# bontor_mbed_rev_c.net
KiCad netlist of a schematic drawn in EAGLE
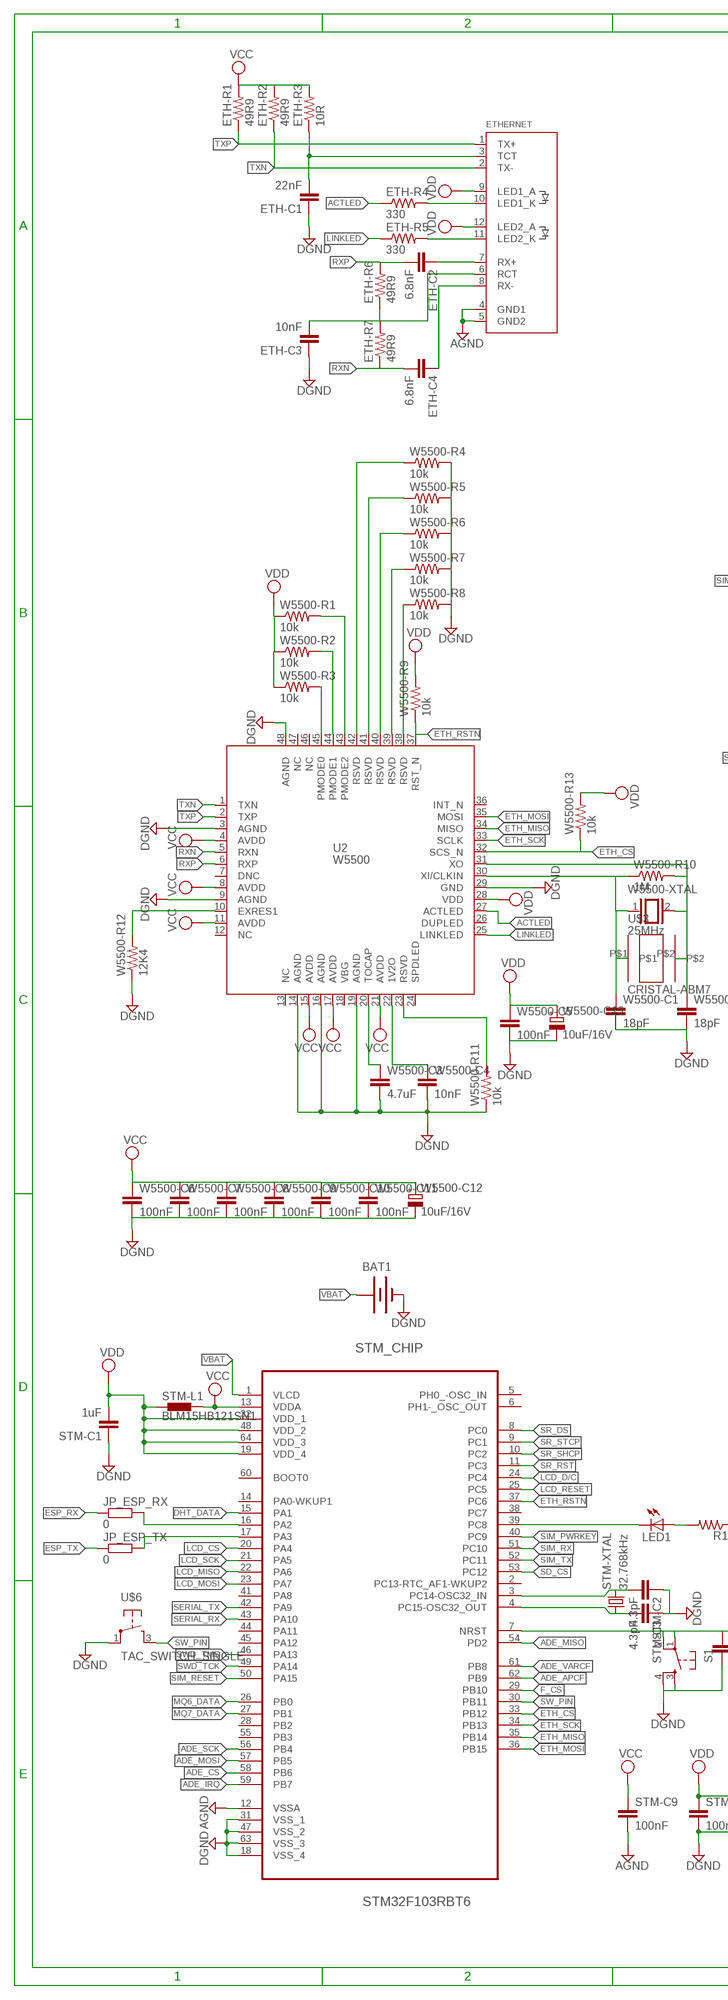
[diagram p0: schematic, sheet 1, part 1 of 2]
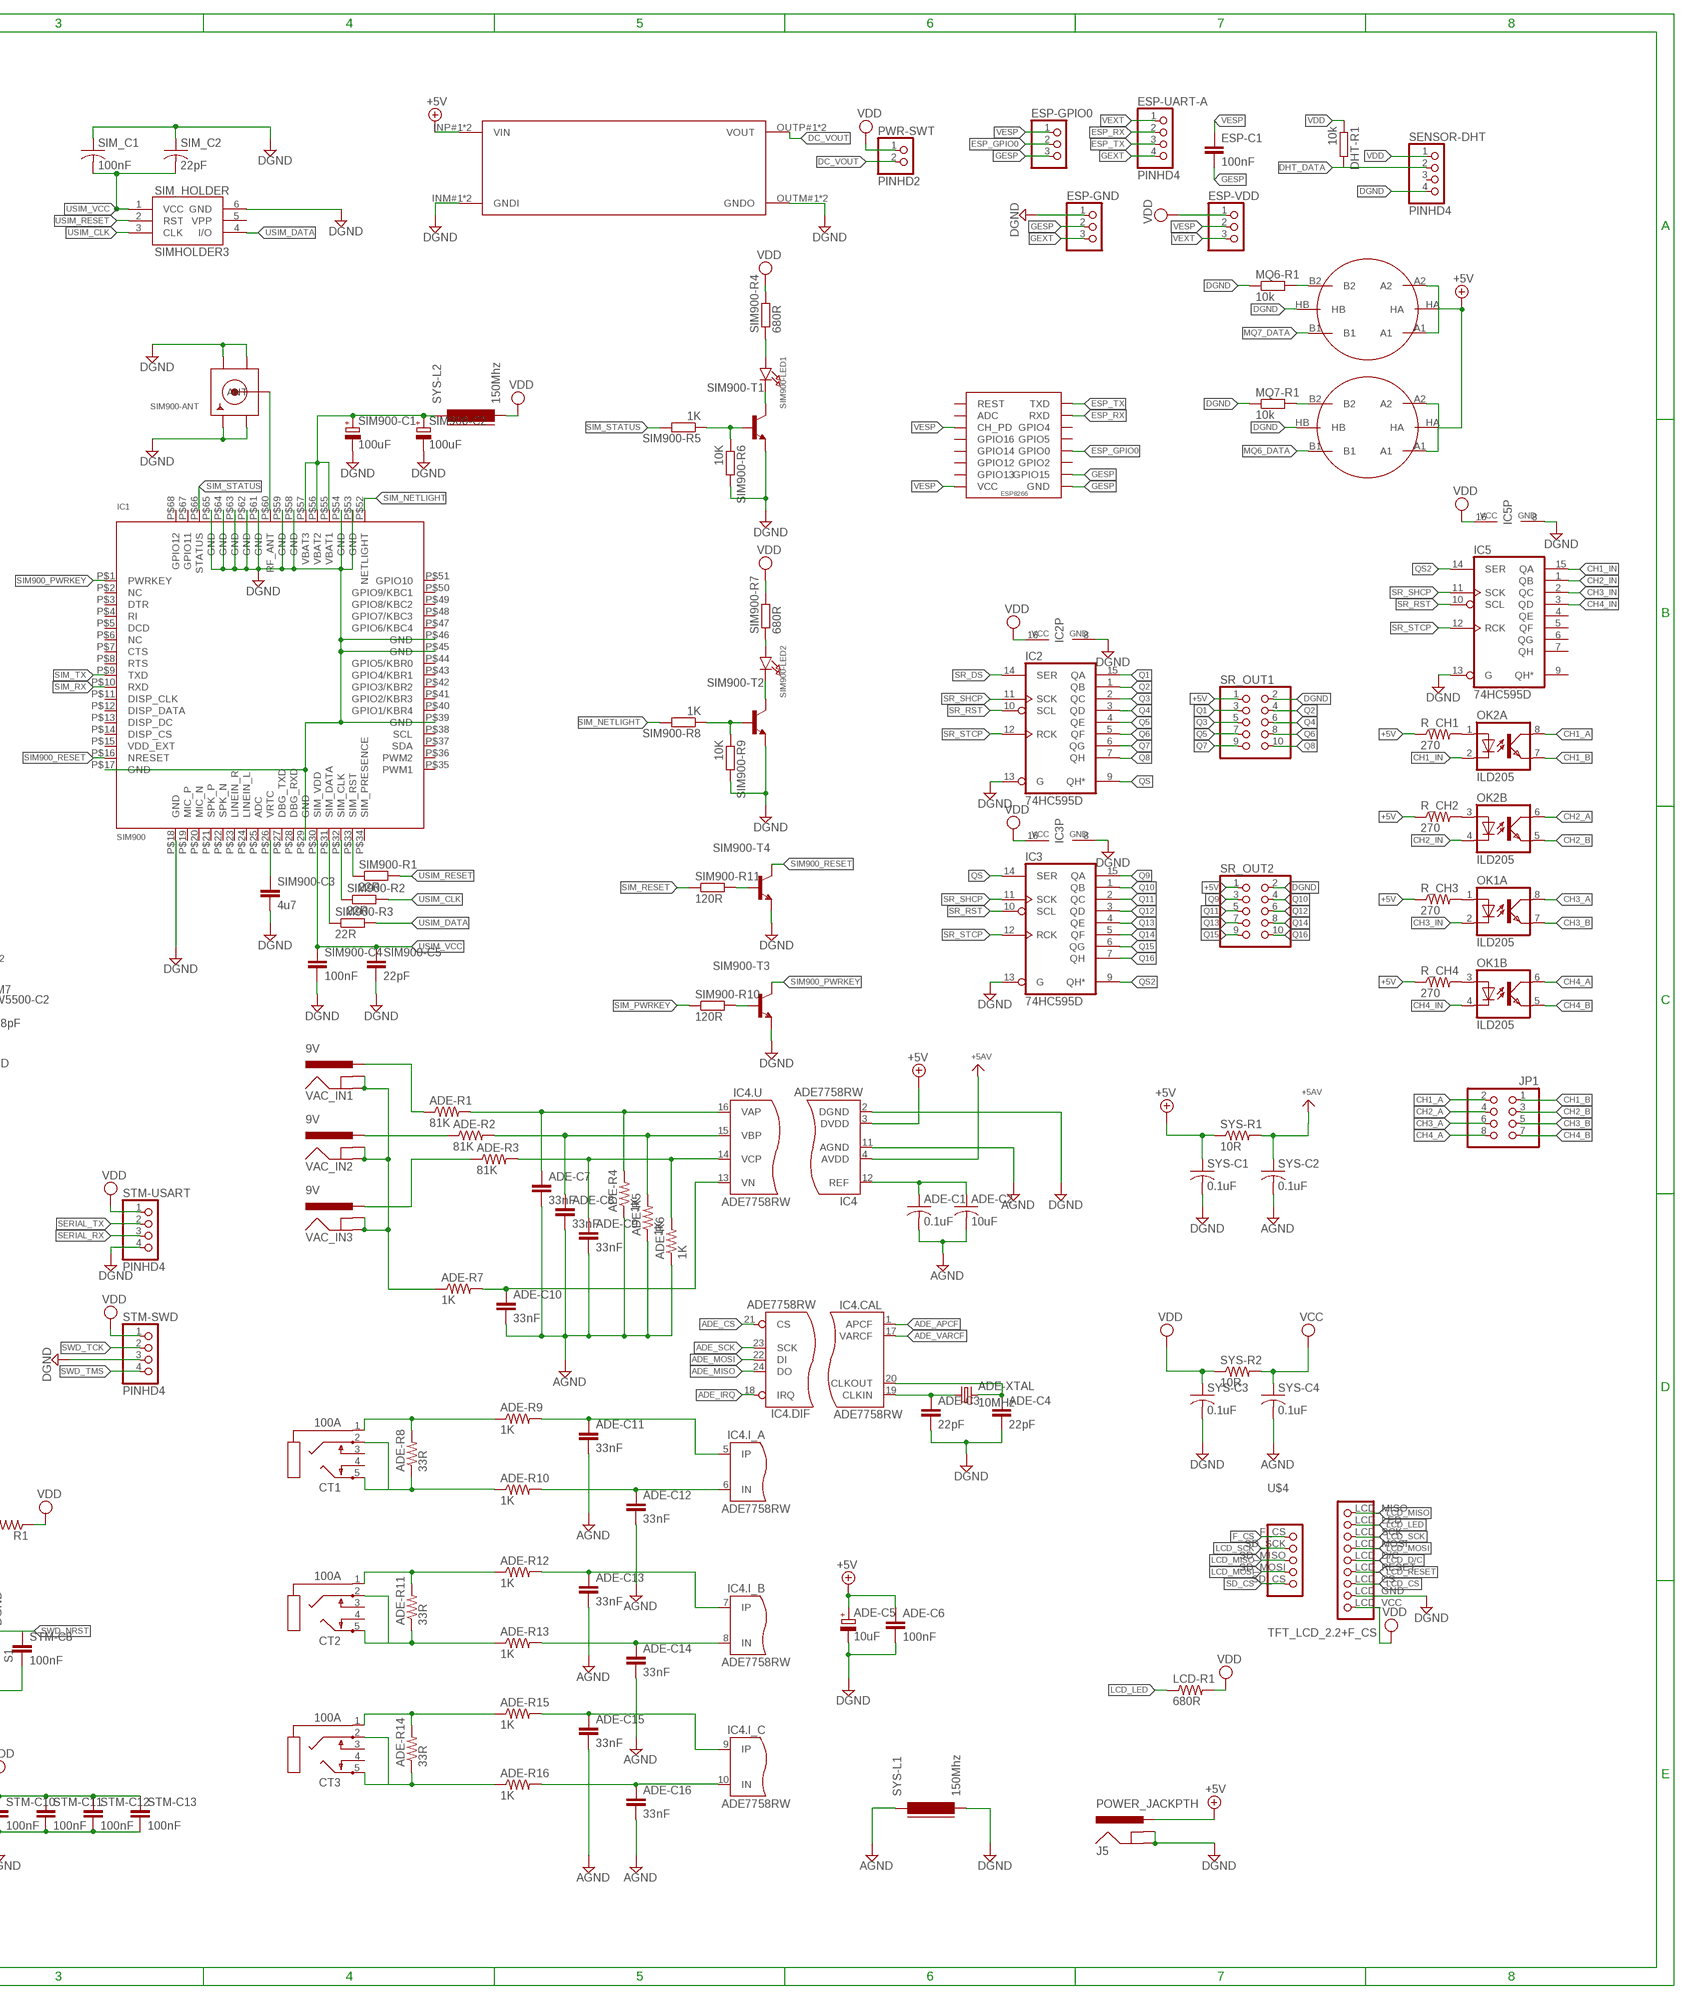
[diagram p1: schematic, sheet 1, part 2 of 2]

(export (version "E")
  (design (tool "Eeschema 10.0.6"))
  (components
    (comp (ref "ADE-C1")
      (value "0.1uF")
      (footprint "eagle-import:C0603@1")
      (libsource (lib "eagle-import") (part "C-USC0603"))
    )
    (comp (ref "ADE-C2")
      (value "10uF")
      (footprint "eagle-import:C0805K")
      (libsource (lib "eagle-import") (part "C-USC0805K"))
    )
    (comp (ref "ADE-C3")
      (value "22pF")
      (footprint "eagle-import:C0603")
      (libsource (lib "eagle-import") (part "C-EUC0603"))
    )
    (comp (ref "ADE-C4")
      (value "22pF")
      (footprint "eagle-import:C0603")
      (libsource (lib "eagle-import") (part "C-EUC0603"))
    )
    (comp (ref "ADE-C5")
      (value "10uF")
      (footprint "eagle-import:153CLV-0605")
      (libsource (lib "eagle-import") (part "CPOL-EU153CLV-0605"))
    )
    (comp (ref "ADE-C6")
      (value "100nF")
      (footprint "eagle-import:C0603")
      (libsource (lib "eagle-import") (part "C-EUC0603"))
    )
    (comp (ref "ADE-C7")
      (value "33nF")
      (footprint "eagle-import:0603-CAP")
      (libsource (lib "eagle-import") (part "CAP0603-CAP"))
    )
    (comp (ref "ADE-C8")
      (value "33nF")
      (footprint "eagle-import:0603-CAP")
      (libsource (lib "eagle-import") (part "CAP0603-CAP"))
    )
    (comp (ref "ADE-C9")
      (value "33nF")
      (footprint "eagle-import:0603-CAP")
      (libsource (lib "eagle-import") (part "CAP0603-CAP"))
    )
    (comp (ref "ADE-C10")
      (value "33nF")
      (footprint "eagle-import:0603-CAP")
      (libsource (lib "eagle-import") (part "CAP0603-CAP"))
    )
    (comp (ref "ADE-C11")
      (value "33nF")
      (footprint "eagle-import:0603-CAP")
      (libsource (lib "eagle-import") (part "CAP0603-CAP"))
    )
    (comp (ref "ADE-C12")
      (value "33nF")
      (footprint "eagle-import:0603-CAP")
      (libsource (lib "eagle-import") (part "CAP0603-CAP"))
    )
    (comp (ref "ADE-C13")
      (value "33nF")
      (footprint "eagle-import:0603-CAP")
      (libsource (lib "eagle-import") (part "CAP0603-CAP"))
    )
    (comp (ref "ADE-C14")
      (value "33nF")
      (footprint "eagle-import:0603-CAP")
      (libsource (lib "eagle-import") (part "CAP0603-CAP"))
    )
    (comp (ref "ADE-C15")
      (value "33nF")
      (footprint "eagle-import:0603-CAP")
      (libsource (lib "eagle-import") (part "CAP0603-CAP"))
    )
    (comp (ref "ADE-C16")
      (value "33nF")
      (footprint "eagle-import:0603-CAP")
      (libsource (lib "eagle-import") (part "CAP0603-CAP"))
    )
    (comp (ref "ADE-R1")
      (value "81K")
      (footprint "eagle-import:0603-RES")
      (libsource (lib "eagle-import") (part "SparkFun-Passives_RESISTOR0603-RES"))
    )
    (comp (ref "ADE-R2")
      (value "81K")
      (footprint "eagle-import:0603-RES")
      (libsource (lib "eagle-import") (part "SparkFun-Passives_RESISTOR0603-RES"))
    )
    (comp (ref "ADE-R3")
      (value "81K")
      (footprint "eagle-import:0603-RES")
      (libsource (lib "eagle-import") (part "SparkFun-Passives_RESISTOR0603-RES"))
    )
    (comp (ref "ADE-R4")
      (value "1K")
      (footprint "eagle-import:0603-RES")
      (libsource (lib "eagle-import") (part "SparkFun-Passives_RESISTOR0603-RES"))
    )
    (comp (ref "ADE-R5")
      (value "1K")
      (footprint "eagle-import:0603-RES")
      (libsource (lib "eagle-import") (part "SparkFun-Passives_RESISTOR0603-RES"))
    )
    (comp (ref "ADE-R6")
      (value "1K")
      (footprint "eagle-import:0603-RES")
      (libsource (lib "eagle-import") (part "SparkFun-Passives_RESISTOR0603-RES"))
    )
    (comp (ref "ADE-R7")
      (value "1K")
      (footprint "eagle-import:0603-RES")
      (libsource (lib "eagle-import") (part "SparkFun-Passives_RESISTOR0603-RES"))
    )
    (comp (ref "ADE-R8")
      (value "33R")
      (footprint "eagle-import:0603-RES")
      (libsource (lib "eagle-import") (part "SparkFun-Passives_RESISTOR0603-RES"))
    )
    (comp (ref "ADE-R9")
      (value "1K")
      (footprint "eagle-import:0603-RES")
      (libsource (lib "eagle-import") (part "SparkFun-Passives_RESISTOR0603-RES"))
    )
    (comp (ref "ADE-R10")
      (value "1K")
      (footprint "eagle-import:0603-RES")
      (libsource (lib "eagle-import") (part "SparkFun-Passives_RESISTOR0603-RES"))
    )
    (comp (ref "ADE-R11")
      (value "33R")
      (footprint "eagle-import:0603-RES")
      (libsource (lib "eagle-import") (part "SparkFun-Passives_RESISTOR0603-RES"))
    )
    (comp (ref "ADE-R12")
      (value "1K")
      (footprint "eagle-import:0603-RES")
      (libsource (lib "eagle-import") (part "SparkFun-Passives_RESISTOR0603-RES"))
    )
    (comp (ref "ADE-R13")
      (value "1K")
      (footprint "eagle-import:0603-RES")
      (libsource (lib "eagle-import") (part "SparkFun-Passives_RESISTOR0603-RES"))
    )
    (comp (ref "ADE-R14")
      (value "33R")
      (footprint "eagle-import:0603-RES")
      (libsource (lib "eagle-import") (part "SparkFun-Passives_RESISTOR0603-RES"))
    )
    (comp (ref "ADE-R15")
      (value "1K")
      (footprint "eagle-import:0603-RES")
      (libsource (lib "eagle-import") (part "SparkFun-Passives_RESISTOR0603-RES"))
    )
    (comp (ref "ADE-R16")
      (value "1K")
      (footprint "eagle-import:0603-RES")
      (libsource (lib "eagle-import") (part "SparkFun-Passives_RESISTOR0603-RES"))
    )
    (comp (ref "ADE-XTAL")
      (value "10MHz")
      (footprint "eagle-import:HC49US")
      (libsource (lib "eagle-import") (part "CRYSTALHC49US"))
    )
    (comp (ref "BAT1")
      (value "BATTERY20PTH")
      (footprint "eagle-import:BATTCOM_20MM_PTH")
      (libsource (lib "eagle-import") (part "BATTERY20PTH"))
    )
    (comp (ref "CT1")
      (value "100A")
      (footprint "eagle-import:STX3100")
      (libsource (lib "eagle-import") (part "AUDIO_STEREOJACK"))
    )
    (comp (ref "CT2")
      (value "100A")
      (footprint "eagle-import:STX3100")
      (libsource (lib "eagle-import") (part "AUDIO_STEREOJACK"))
    )
    (comp (ref "CT3")
      (value "100A")
      (footprint "eagle-import:STX3100")
      (libsource (lib "eagle-import") (part "AUDIO_STEREOJACK"))
    )
    (comp (ref "DCDC-3.5V")
      (value "DCDCMODULE_SMALL")
      (footprint "eagle-import:DCDCMODULE-SMALL")
      (libsource (lib "eagle-import") (part "DCDCMODULE_SMALL"))
    )
    (comp (ref "DHT-R1")
      (value "10k")
      (footprint "eagle-import:R0603")
      (libsource (lib "eagle-import") (part "resistor_R-EU_R0603"))
    )
    (comp (ref "ESP-C1")
      (value "100nF")
      (footprint "eagle-import:C0603")
      (libsource (lib "eagle-import") (part "C-EUC0603"))
    )
    (comp (ref "ESP-GND")
      (value "PINHD-1X3")
      (footprint "eagle-import:1X03")
      (libsource (lib "eagle-import") (part "PINHD-1X3"))
    )
    (comp (ref "ESP-GPIO0")
      (value "PINHD-1X3")
      (footprint "eagle-import:1X03")
      (libsource (lib "eagle-import") (part "PINHD-1X3"))
    )
    (comp (ref "ESP-UART-A")
      (value "PINHD4")
      (footprint "eagle-import:PINHD4")
      (libsource (lib "eagle-import") (part "PINHD4"))
    )
    (comp (ref "ESP-VDD")
      (value "PINHD-1X3")
      (footprint "eagle-import:1X03")
      (libsource (lib "eagle-import") (part "PINHD-1X3"))
    )
    (comp (ref "ETH-C1")
      (value "22nF")
      (footprint "eagle-import:C0603")
      (libsource (lib "eagle-import") (part "C-EUC0603"))
    )
    (comp (ref "ETH-C2")
      (value "6.8nF")
      (footprint "eagle-import:C0603")
      (libsource (lib "eagle-import") (part "C-EUC0603"))
    )
    (comp (ref "ETH-C3")
      (value "10nF")
      (footprint "eagle-import:C0603")
      (libsource (lib "eagle-import") (part "C-EUC0603"))
    )
    (comp (ref "ETH-C4")
      (value "6.8nF")
      (footprint "eagle-import:C0603")
      (libsource (lib "eagle-import") (part "C-EUC0603"))
    )
    (comp (ref "ETH-R1")
      (value "49R9")
      (footprint "eagle-import:R0603")
      (libsource (lib "eagle-import") (part "R-US_R0603"))
    )
    (comp (ref "ETH-R2")
      (value "49R9")
      (footprint "eagle-import:R0603")
      (libsource (lib "eagle-import") (part "R-US_R0603"))
    )
    (comp (ref "ETH-R3")
      (value "10R")
      (footprint "eagle-import:R0603")
      (libsource (lib "eagle-import") (part "R-US_R0603"))
    )
    (comp (ref "ETH-R4")
      (value "330")
      (footprint "eagle-import:R0603")
      (libsource (lib "eagle-import") (part "R-US_R0603"))
    )
    (comp (ref "ETH-R5")
      (value "330")
      (footprint "eagle-import:R0603")
      (libsource (lib "eagle-import") (part "R-US_R0603"))
    )
    (comp (ref "ETH-R6")
      (value "49R9")
      (footprint "eagle-import:R0603")
      (libsource (lib "eagle-import") (part "R-US_R0603"))
    )
    (comp (ref "ETH-R7")
      (value "49R9")
      (footprint "eagle-import:R0603")
      (libsource (lib "eagle-import") (part "R-US_R0603"))
    )
    (comp (ref "ETHERNET")
      (value "RJ45J0026D21BNL")
      (footprint "eagle-import:RJ45_PULSEJACK")
      (libsource (lib "eagle-import") (part "RJ45J0026D21BNL"))
    )
    (comp (ref "IC1")
      (value "SIM900")
      (footprint "eagle-import:SIM900_SMT")
      (libsource (lib "eagle-import") (part "GSM_SIM900_LITERAL"))
    )
    (comp (ref "IC2")
      (value "74HC595D")
      (footprint "eagle-import:SO16")
      (libsource (lib "eagle-import") (part "74595DHC"))
    )
    (comp (ref "IC3")
      (value "74HC595D")
      (footprint "eagle-import:SO16")
      (libsource (lib "eagle-import") (part "74595DHC"))
    )
    (comp (ref "IC4")
      (value "ADE7758RW")
      (footprint "eagle-import:SOIC24")
      (libsource (lib "eagle-import") (part "ADE7758RW"))
    )
    (comp (ref "IC5")
      (value "74HC595D")
      (footprint "eagle-import:SO16")
      (libsource (lib "eagle-import") (part "74595DHC"))
    )
    (comp (ref "J5")
      (value "POWER_JACKPTH")
      (footprint "eagle-import:POWER_JACK_PTH")
      (libsource (lib "eagle-import") (part "POWER_JACKPTH"))
    )
    (comp (ref "JP1")
      (value "PINHD-2X4")
      (footprint "eagle-import:2X04")
      (libsource (lib "eagle-import") (part "PINHD-2X4"))
    )
    (comp (ref "JP_ESP_RX")
      (value "0")
      (footprint "eagle-import:R0201")
      (libsource (lib "eagle-import") (part "R-EU_R0201"))
    )
    (comp (ref "JP_ESP_TX")
      (value "0")
      (footprint "eagle-import:R0201")
      (libsource (lib "eagle-import") (part "R-EU_R0201"))
    )
    (comp (ref "LCD-R1")
      (value "680R")
      (footprint "eagle-import:0603-RES")
      (libsource (lib "eagle-import") (part "SparkFun-Passives_RESISTOR0603-RES"))
    )
    (comp (ref "LED1")
      (value "LEDCHIPLED_0603")
      (footprint "eagle-import:CHIPLED_0603")
      (libsource (lib "eagle-import") (part "LEDCHIPLED_0603"))
    )
    (comp (ref "MQ6-R1")
      (value "10k")
      (footprint "eagle-import:R0603")
      (libsource (lib "eagle-import") (part "resistor_R-EU_R0603"))
    )
    (comp (ref "MQ7-R1")
      (value "10k")
      (footprint "eagle-import:R0603")
      (libsource (lib "eagle-import") (part "resistor_R-EU_R0603"))
    )
    (comp (ref "OK1")
      (value "ILD205")
      (footprint "eagle-import:SOIC08")
      (fields (field (name "MF") "VISHAY/TELEFUNKEN") (field (name "MPN") "ILD205T"))
      (libsource (lib "eagle-import") (part "ILD205"))
    )
    (comp (ref "OK2")
      (value "ILD205")
      (footprint "eagle-import:SOIC08")
      (fields (field (name "MF") "VISHAY/TELEFUNKEN") (field (name "MPN") "ILD205T"))
      (libsource (lib "eagle-import") (part "ILD205"))
    )
    (comp (ref "PWR-SWT")
      (value "PINHD2")
      (footprint "eagle-import:PINHD2")
      (libsource (lib "eagle-import") (part "PINHD2"))
    )
    (comp (ref "R1")
      (value "RESISTOR0603-RES")
      (footprint "eagle-import:0603-RES")
      (libsource (lib "eagle-import") (part "RESISTOR0603-RES"))
    )
    (comp (ref "R_CH1")
      (value "270")
      (footprint "eagle-import:0603-RES")
      (libsource (lib "eagle-import") (part "SparkFun-Passives_RESISTOR0603-RES"))
    )
    (comp (ref "R_CH2")
      (value "270")
      (footprint "eagle-import:0603-RES")
      (libsource (lib "eagle-import") (part "SparkFun-Passives_RESISTOR0603-RES"))
    )
    (comp (ref "R_CH3")
      (value "270")
      (footprint "eagle-import:0603-RES")
      (libsource (lib "eagle-import") (part "SparkFun-Passives_RESISTOR0603-RES"))
    )
    (comp (ref "R_CH4")
      (value "270")
      (footprint "eagle-import:0603-RES")
      (libsource (lib "eagle-import") (part "SparkFun-Passives_RESISTOR0603-RES"))
    )
    (comp (ref "S1")
      (value "TAC_SWITCHPTH")
      (footprint "eagle-import:TACTILE-PTH")
      (libsource (lib "eagle-import") (part "TAC_SWITCHPTH"))
    )
    (comp (ref "SENSOR-DHT")
      (value "PINHD4")
      (footprint "eagle-import:PINHD4")
      (libsource (lib "eagle-import") (part "PINHD4"))
    )
    (comp (ref "SENSOR-MQ6")
      (value "METHANE_SENSOR")
      (footprint "eagle-import:MQ-3")
      (libsource (lib "eagle-import") (part "METHANE_SENSOR"))
    )
    (comp (ref "SENSOR-MQ7")
      (value "METHANE_SENSOR")
      (footprint "eagle-import:MQ-3")
      (libsource (lib "eagle-import") (part "METHANE_SENSOR"))
    )
    (comp (ref "SIM900-ANT")
      (value "SMACONNECTOR")
      (footprint "eagle-import:SMA90_DIP")
      (libsource (lib "eagle-import") (part "SMACONNECTOR"))
    )
    (comp (ref "SIM900-C1")
      (value "100uF")
      (footprint "eagle-import:153CLV-0605")
      (libsource (lib "eagle-import") (part "CPOL-EU153CLV-0605"))
    )
    (comp (ref "SIM900-C2")
      (value "100uF")
      (footprint "eagle-import:153CLV-0605")
      (libsource (lib "eagle-import") (part "CPOL-EU153CLV-0605"))
    )
    (comp (ref "SIM900-C3")
      (value "4u7")
      (footprint "eagle-import:C0603")
      (libsource (lib "eagle-import") (part "C-EUC0603"))
    )
    (comp (ref "SIM900-C4")
      (value "100nF")
      (footprint "eagle-import:C0603")
      (libsource (lib "eagle-import") (part "C-EUC0603"))
    )
    (comp (ref "SIM900-C5")
      (value "22pF")
      (footprint "eagle-import:C0603")
      (libsource (lib "eagle-import") (part "C-EUC0603"))
    )
    (comp (ref "SIM900-LED1")
      (value "LED0805_NOOUTLINE")
      (footprint "eagle-import:CHIPLED_0805_NOOUTLINE")
      (libsource (lib "eagle-import") (part "LED0805_NOOUTLINE"))
    )
    (comp (ref "SIM900-LED2")
      (value "LED0805_NOOUTLINE")
      (footprint "eagle-import:CHIPLED_0805_NOOUTLINE")
      (libsource (lib "eagle-import") (part "LED0805_NOOUTLINE"))
    )
    (comp (ref "SIM900-R1")
      (value "22R")
      (footprint "eagle-import:R0603")
      (libsource (lib "eagle-import") (part "R-EU_R0603"))
    )
    (comp (ref "SIM900-R2")
      (value "22R")
      (footprint "eagle-import:R0603")
      (libsource (lib "eagle-import") (part "R-EU_R0603"))
    )
    (comp (ref "SIM900-R3")
      (value "22R")
      (footprint "eagle-import:R0603")
      (libsource (lib "eagle-import") (part "R-EU_R0603"))
    )
    (comp (ref "SIM900-R4")
      (value "680R")
      (footprint "eagle-import:R0603")
      (libsource (lib "eagle-import") (part "R-EU_R0603"))
    )
    (comp (ref "SIM900-R5")
      (value "1K")
      (footprint "eagle-import:R0603")
      (libsource (lib "eagle-import") (part "R-EU_R0603"))
    )
    (comp (ref "SIM900-R6")
      (value "10K")
      (footprint "eagle-import:R0603")
      (libsource (lib "eagle-import") (part "R-EU_R0603"))
    )
    (comp (ref "SIM900-R7")
      (value "680R")
      (footprint "eagle-import:R0603")
      (libsource (lib "eagle-import") (part "R-EU_R0603"))
    )
    (comp (ref "SIM900-R8")
      (value "1K")
      (footprint "eagle-import:R0603")
      (libsource (lib "eagle-import") (part "R-EU_R0603"))
    )
    (comp (ref "SIM900-R9")
      (value "10K")
      (footprint "eagle-import:R0603")
      (libsource (lib "eagle-import") (part "R-EU_R0603"))
    )
    (comp (ref "SIM900-R10")
      (value "120R")
      (footprint "eagle-import:R0603")
      (libsource (lib "eagle-import") (part "resistor_R-EU_R0603"))
    )
    (comp (ref "SIM900-R11")
      (value "120R")
      (footprint "eagle-import:R0603")
      (libsource (lib "eagle-import") (part "resistor_R-EU_R0603"))
    )
    (comp (ref "SIM900-T1")
      (value "MMBT2222ALT1-NPN-SOT23-BEC")
      (footprint "eagle-import:SOT23-BEC")
      (libsource (lib "eagle-import") (part "-NPN-SOT23-BECMMBT2222ALT1"))
    )
    (comp (ref "SIM900-T2")
      (value "MMBT2222ALT1-NPN-SOT23-BEC")
      (footprint "eagle-import:SOT23-BEC")
      (libsource (lib "eagle-import") (part "-NPN-SOT23-BECMMBT2222ALT1"))
    )
    (comp (ref "SIM900-T3")
      (value "MMBT2222ALT1-NPN-SOT23-BEC")
      (footprint "eagle-import:SOT23-BEC")
      (libsource (lib "eagle-import") (part "transistor-neu-to92_-NPN-SOT23-BECMMBT2222ALT1"))
    )
    (comp (ref "SIM900-T4")
      (value "MMBT2222ALT1-NPN-SOT23-BEC")
      (footprint "eagle-import:SOT23-BEC")
      (libsource (lib "eagle-import") (part "transistor-neu-to92_-NPN-SOT23-BECMMBT2222ALT1"))
    )
    (comp (ref "SIM_C1")
      (value "100nF")
      (footprint "eagle-import:C0603K")
      (libsource (lib "eagle-import") (part "C-USC0603K"))
    )
    (comp (ref "SIM_C2")
      (value "22pF")
      (footprint "eagle-import:C0603K")
      (libsource (lib "eagle-import") (part "C-USC0603K"))
    )
    (comp (ref "SIM_HOLDER")
      (value "SIMHOLDER3")
      (footprint "eagle-import:SIMHOLDER3")
      (libsource (lib "eagle-import") (part "SIMHOLDER3"))
    )
    (comp (ref "SR_OUT1")
      (value "PINHD-2X5/90")
      (footprint "eagle-import:2X05_90")
      (libsource (lib "eagle-import") (part "PINHD-2X5/90"))
    )
    (comp (ref "SR_OUT2")
      (value "PINHD-2X5/90")
      (footprint "eagle-import:2X05_90")
      (libsource (lib "eagle-import") (part "PINHD-2X5/90"))
    )
    (comp (ref "STM-C1")
      (value "1uF")
      (footprint "eagle-import:C0603")
      (libsource (lib "eagle-import") (part "C-EUC0603"))
    )
    (comp (ref "STM-C2")
      (value "4.3pF")
      (footprint "eagle-import:C0603")
      (libsource (lib "eagle-import") (part "C-EUC0603"))
    )
    (comp (ref "STM-C3")
      (value "4.3pF")
      (footprint "eagle-import:C0603")
      (libsource (lib "eagle-import") (part "C-EUC0603"))
    )
    (comp (ref "STM-C8")
      (value "100nF")
      (footprint "eagle-import:C0603")
      (libsource (lib "eagle-import") (part "C-EUC0603"))
    )
    (comp (ref "STM-C9")
      (value "100nF")
      (footprint "eagle-import:C0603")
      (libsource (lib "eagle-import") (part "C-EUC0603"))
    )
    (comp (ref "STM-C10")
      (value "100nF")
      (footprint "eagle-import:C0603")
      (libsource (lib "eagle-import") (part "C-EUC0603"))
    )
    (comp (ref "STM-C11")
      (value "100nF")
      (footprint "eagle-import:C0603")
      (libsource (lib "eagle-import") (part "C-EUC0603"))
    )
    (comp (ref "STM-C12")
      (value "100nF")
      (footprint "eagle-import:C0603")
      (libsource (lib "eagle-import") (part "C-EUC0603"))
    )
    (comp (ref "STM-C13")
      (value "100nF")
      (footprint "eagle-import:C0603")
      (libsource (lib "eagle-import") (part "C-EUC0603"))
    )
    (comp (ref "STM-L1")
      (value "BLM15HB121SN1")
      (footprint "eagle-import:0402")
      (libsource (lib "eagle-import") (part "BLM15HB121SN1"))
    )
    (comp (ref "STM-SWD")
      (value "PINHD4")
      (footprint "eagle-import:PINHD4")
      (libsource (lib "eagle-import") (part "PINHD4"))
    )
    (comp (ref "STM-USART")
      (value "PINHD4")
      (footprint "eagle-import:PINHD4")
      (libsource (lib "eagle-import") (part "PINHD4"))
    )
    (comp (ref "STM-XTAL")
      (value "32.768kHz")
      (footprint "eagle-import:TC26H")
      (libsource (lib "eagle-import") (part "CRYSTALTC26H"))
    )
    (comp (ref "STM_CHIP")
      (value "STM32F103RBT6")
      (footprint "eagle-import:QFP50P1200X1200X160-64N")
      (fields (field (name "MPN") "STM32L152RBT6"))
      (libsource (lib "eagle-import") (part "STM32L152RBT6"))
    )
    (comp (ref "SYS-C1")
      (value "0.1uF")
      (footprint "eagle-import:C0603@1")
      (libsource (lib "eagle-import") (part "C-USC0603"))
    )
    (comp (ref "SYS-C2")
      (value "0.1uF")
      (footprint "eagle-import:C0603@1")
      (libsource (lib "eagle-import") (part "C-USC0603"))
    )
    (comp (ref "SYS-C3")
      (value "0.1uF")
      (footprint "eagle-import:C0603@1")
      (libsource (lib "eagle-import") (part "C-USC0603"))
    )
    (comp (ref "SYS-C4")
      (value "0.1uF")
      (footprint "eagle-import:C0603@1")
      (libsource (lib "eagle-import") (part "C-USC0603"))
    )
    (comp (ref "SYS-L1")
      (value "150Mhz")
      (footprint "eagle-import:FB805")
      (libsource (lib "eagle-import") (part "FERRITE-0805"))
    )
    (comp (ref "SYS-L2")
      (value "150Mhz")
      (footprint "eagle-import:FB805")
      (libsource (lib "eagle-import") (part "FERRITE-0805"))
    )
    (comp (ref "SYS-R1")
      (value "10R")
      (footprint "eagle-import:0603-RES")
      (libsource (lib "eagle-import") (part "SparkFun-Passives_RESISTOR0603-RES"))
    )
    (comp (ref "SYS-R2")
      (value "10R")
      (footprint "eagle-import:0603-RES")
      (libsource (lib "eagle-import") (part "SparkFun-Passives_RESISTOR0603-RES"))
    )
    (comp (ref "U$3")
      (value "CRISTAL-ABM7")
      (footprint "eagle-import:CRISTAL-ABM7")
      (libsource (lib "eagle-import") (part "CRISTAL-ABM7"))
    )
    (comp (ref "U$4")
      (value "TFT_LCD_2.2+F_CS")
      (footprint "eagle-import:TFT_LCD_2.2+F_CS")
      (libsource (lib "eagle-import") (part "TFT_LCD_2.2+F_CS"))
    )
    (comp (ref "U$5")
      (value "ESP8266WI12")
      (footprint "eagle-import:WI12")
      (libsource (lib "eagle-import") (part "ESP8266WI12"))
    )
    (comp (ref "U$6")
      (value "TAC_SWITCH_SINGLE")
      (footprint "eagle-import:TACTILE-PTH-SINGLE")
      (libsource (lib "eagle-import") (part "TAC_SWITCH_SINGLE"))
    )
    (comp (ref "U2")
      (value "W5500")
      (footprint "eagle-import:W5500")
      (libsource (lib "eagle-import") (part "W5500"))
    )
    (comp (ref "VAC_IN1")
      (value "9V")
      (footprint "eagle-import:POWER_JACK_PTH")
      (libsource (lib "eagle-import") (part "POWER_JACKPTH"))
    )
    (comp (ref "VAC_IN2")
      (value "9V")
      (footprint "eagle-import:POWER_JACK_PTH")
      (libsource (lib "eagle-import") (part "POWER_JACKPTH"))
    )
    (comp (ref "VAC_IN3")
      (value "9V")
      (footprint "eagle-import:POWER_JACK_PTH")
      (libsource (lib "eagle-import") (part "POWER_JACKPTH"))
    )
    (comp (ref "W5500-C1")
      (value "18pF")
      (footprint "eagle-import:C0603")
      (libsource (lib "eagle-import") (part "C-EUC0603"))
    )
    (comp (ref "W5500-C2")
      (value "18pF")
      (footprint "eagle-import:C0603")
      (libsource (lib "eagle-import") (part "C-EUC0603"))
    )
    (comp (ref "W5500-C3")
      (value "4.7uF")
      (footprint "eagle-import:C0603")
      (libsource (lib "eagle-import") (part "C-EUC0603"))
    )
    (comp (ref "W5500-C4")
      (value "10nF")
      (footprint "eagle-import:C0603")
      (libsource (lib "eagle-import") (part "C-EUC0603"))
    )
    (comp (ref "W5500-C5")
      (value "100nF")
      (footprint "eagle-import:C0603")
      (libsource (lib "eagle-import") (part "C-EUC0603"))
    )
    (comp (ref "W5500-C6")
      (value "100nF")
      (footprint "eagle-import:C0603")
      (libsource (lib "eagle-import") (part "C-EUC0603"))
    )
    (comp (ref "W5500-C7")
      (value "100nF")
      (footprint "eagle-import:C0603")
      (libsource (lib "eagle-import") (part "C-EUC0603"))
    )
    (comp (ref "W5500-C8")
      (value "100nF")
      (footprint "eagle-import:C0603")
      (libsource (lib "eagle-import") (part "C-EUC0603"))
    )
    (comp (ref "W5500-C9")
      (value "100nF")
      (footprint "eagle-import:C0603")
      (libsource (lib "eagle-import") (part "C-EUC0603"))
    )
    (comp (ref "W5500-C10")
      (value "100nF")
      (footprint "eagle-import:C0603")
      (libsource (lib "eagle-import") (part "C-EUC0603"))
    )
    (comp (ref "W5500-C11")
      (value "100nF")
      (footprint "eagle-import:C0603")
      (libsource (lib "eagle-import") (part "C-EUC0603"))
    )
    (comp (ref "W5500-C12")
      (value "10uF/16V")
      (footprint "eagle-import:153CLV-0605")
      (libsource (lib "eagle-import") (part "CPOL-EU153CLV-0605"))
    )
    (comp (ref "W5500-C13")
      (value "10uF/16V")
      (footprint "eagle-import:153CLV-0605")
      (libsource (lib "eagle-import") (part "CPOL-EU153CLV-0605"))
    )
    (comp (ref "W5500-R1")
      (value "10k")
      (footprint "eagle-import:R0603")
      (libsource (lib "eagle-import") (part "R-US_R0603"))
    )
    (comp (ref "W5500-R2")
      (value "10k")
      (footprint "eagle-import:R0603")
      (libsource (lib "eagle-import") (part "R-US_R0603"))
    )
    (comp (ref "W5500-R3")
      (value "10k")
      (footprint "eagle-import:R0603")
      (libsource (lib "eagle-import") (part "R-US_R0603"))
    )
    (comp (ref "W5500-R4")
      (value "10k")
      (footprint "eagle-import:R0603")
      (libsource (lib "eagle-import") (part "R-US_R0603"))
    )
    (comp (ref "W5500-R5")
      (value "10k")
      (footprint "eagle-import:R0603")
      (libsource (lib "eagle-import") (part "R-US_R0603"))
    )
    (comp (ref "W5500-R6")
      (value "10k")
      (footprint "eagle-import:R0603")
      (libsource (lib "eagle-import") (part "R-US_R0603"))
    )
    (comp (ref "W5500-R7")
      (value "10k")
      (footprint "eagle-import:R0603")
      (libsource (lib "eagle-import") (part "R-US_R0603"))
    )
    (comp (ref "W5500-R8")
      (value "10k")
      (footprint "eagle-import:R0603")
      (libsource (lib "eagle-import") (part "R-US_R0603"))
    )
    (comp (ref "W5500-R9")
      (value "10k")
      (footprint "eagle-import:R0603")
      (libsource (lib "eagle-import") (part "R-US_R0603"))
    )
    (comp (ref "W5500-R10")
      (value "1M")
      (footprint "eagle-import:R0603")
      (libsource (lib "eagle-import") (part "R-US_R0603"))
    )
    (comp (ref "W5500-R11")
      (value "10k")
      (footprint "eagle-import:R0603")
      (libsource (lib "eagle-import") (part "R-US_R0603"))
    )
    (comp (ref "W5500-R12")
      (value "12K4")
      (footprint "eagle-import:R0805")
      (libsource (lib "eagle-import") (part "R-US_R0805"))
    )
    (comp (ref "W5500-R13")
      (value "10k")
      (footprint "eagle-import:R0603")
      (libsource (lib "eagle-import") (part "R-US_R0603"))
    )
    (comp (ref "W5500-XTAL")
      (value "25MHz")
      (footprint "eagle-import:QS")
      (libsource (lib "eagle-import") (part "XTAL/S"))
    )
  )
  (nets
    (net (code "1") (name "+5AV") (class "Default")
      (node (ref "IC4") (pin "4") (pinfunction "AVDD_4") (pintype "power_in"))
      (node (ref "SYS-C2") (pin "1") (pinfunction "1_1") (pintype "passive"))
      (node (ref "SYS-R1") (pin "2") (pinfunction "2_2") (pintype "passive"))
    )
    (net (code "2") (name "+5V") (class "Default")
      (node (ref "ADE-C5") (pin "+") (pinfunction "+_+") (pintype "passive"))
      (node (ref "ADE-C6") (pin "1") (pinfunction "1_1") (pintype "passive"))
      (node (ref "DCDC-3.5V") (pin "INP#1") (pinfunction "VIN_INP#1") (pintype "bidirectional"))
      (node (ref "DCDC-3.5V") (pin "INP#2") (pinfunction "VIN_INP#2") (pintype "bidirectional"))
      (node (ref "IC4") (pin "3") (pinfunction "DVDD_3") (pintype "power_in"))
      (node (ref "J5") (pin "PWR") (pinfunction "PWR_PWR") (pintype "bidirectional"))
      (node (ref "R_CH1") (pin "1") (pinfunction "1_1") (pintype "passive"))
      (node (ref "R_CH2") (pin "1") (pinfunction "1_1") (pintype "passive"))
      (node (ref "R_CH3") (pin "1") (pinfunction "1_1") (pintype "passive"))
      (node (ref "R_CH4") (pin "1") (pinfunction "1_1") (pintype "passive"))
      (node (ref "SENSOR-MQ6") (pin "A1") (pinfunction "A1_A1") (pintype "bidirectional"))
      (node (ref "SENSOR-MQ6") (pin "A2") (pinfunction "A2_A2") (pintype "bidirectional"))
      (node (ref "SENSOR-MQ6") (pin "HA") (pinfunction "HA_HA") (pintype "bidirectional"))
      (node (ref "SENSOR-MQ7") (pin "A1") (pinfunction "A1_A1") (pintype "bidirectional"))
      (node (ref "SENSOR-MQ7") (pin "A2") (pinfunction "A2_A2") (pintype "bidirectional"))
      (node (ref "SENSOR-MQ7") (pin "HA") (pinfunction "HA_HA") (pintype "bidirectional"))
      (node (ref "SR_OUT1") (pin "1") (pinfunction "1_1") (pintype "passive"))
      (node (ref "SR_OUT2") (pin "1") (pinfunction "1_1") (pintype "passive"))
      (node (ref "SYS-C1") (pin "1") (pinfunction "1_1") (pintype "passive"))
      (node (ref "SYS-R1") (pin "1") (pinfunction "1_1") (pintype "passive"))
    )
    (net (code "3") (name "/GPIO11") (class "Default")
      (node (ref "IC1") (pin "P$67") (pinfunction "GPIO11_P$67") (pintype "power_in"))
    )
    (net (code "4") (name "/GPIO12") (class "Default")
      (node (ref "IC1") (pin "P$68") (pinfunction "GPIO12_P$68") (pintype "power_in"))
    )
    (net (code "5") (name "ACTLED") (class "Default")
      (node (ref "ETH-R4") (pin "1") (pinfunction "1_1") (pintype "passive"))
      (node (ref "U2") (pin "27") (pinfunction "ACTLED_27") (pintype "passive"))
    )
    (net (code "6") (name "ADE_APCF") (class "Default")
      (node (ref "IC4") (pin "1") (pinfunction "APCF_1") (pintype "output"))
      (node (ref "STM_CHIP") (pin "62") (pinfunction "PB9_62") (pintype "bidirectional"))
    )
    (net (code "7") (name "ADE_CS") (class "Default")
      (node (ref "IC4") (pin "21") (pinfunction "CS_21") (pintype "input"))
      (node (ref "STM_CHIP") (pin "58") (pinfunction "PB6_58") (pintype "bidirectional"))
    )
    (net (code "8") (name "ADE_IRQ") (class "Default")
      (node (ref "IC4") (pin "18") (pinfunction "IRQ_18") (pintype "output"))
      (node (ref "STM_CHIP") (pin "59") (pinfunction "PB7_59") (pintype "bidirectional"))
    )
    (net (code "9") (name "ADE_MISO") (class "Default")
      (node (ref "IC4") (pin "24") (pinfunction "DO_24") (pintype "output"))
      (node (ref "STM_CHIP") (pin "54") (pinfunction "PD2_54") (pintype "bidirectional"))
    )
    (net (code "10") (name "ADE_MOSI") (class "Default")
      (node (ref "IC4") (pin "22") (pinfunction "DI_22") (pintype "input"))
      (node (ref "STM_CHIP") (pin "57") (pinfunction "PB5_57") (pintype "bidirectional"))
    )
    (net (code "11") (name "ADE_SCK") (class "Default")
      (node (ref "IC4") (pin "23") (pinfunction "SCK_23") (pintype "input"))
      (node (ref "STM_CHIP") (pin "56") (pinfunction "PB4_56") (pintype "bidirectional"))
    )
    (net (code "12") (name "ADE_VARCF") (class "Default")
      (node (ref "IC4") (pin "17") (pinfunction "VARCF_17") (pintype "output"))
      (node (ref "STM_CHIP") (pin "61") (pinfunction "PB8_61") (pintype "bidirectional"))
    )
    (net (code "13") (name "AGND") (class "Default")
      (node (ref "ADE-C1") (pin "2") (pinfunction "2_2") (pintype "passive"))
      (node (ref "ADE-C10") (pin "2") (pinfunction "2_2") (pintype "passive"))
      (node (ref "ADE-C11") (pin "2") (pinfunction "2_2") (pintype "passive"))
      (node (ref "ADE-C12") (pin "2") (pinfunction "2_2") (pintype "passive"))
      (node (ref "ADE-C13") (pin "2") (pinfunction "2_2") (pintype "passive"))
      (node (ref "ADE-C14") (pin "2") (pinfunction "2_2") (pintype "passive"))
      (node (ref "ADE-C15") (pin "2") (pinfunction "2_2") (pintype "passive"))
      (node (ref "ADE-C16") (pin "2") (pinfunction "2_2") (pintype "passive"))
      (node (ref "ADE-C2") (pin "2") (pinfunction "2_2") (pintype "passive"))
      (node (ref "ADE-C7") (pin "2") (pinfunction "2_2") (pintype "passive"))
      (node (ref "ADE-C8") (pin "2") (pinfunction "2_2") (pintype "passive"))
      (node (ref "ADE-C9") (pin "2") (pinfunction "2_2") (pintype "passive"))
      (node (ref "ADE-R4") (pin "1") (pinfunction "1_1") (pintype "passive"))
      (node (ref "ADE-R5") (pin "1") (pinfunction "1_1") (pintype "passive"))
      (node (ref "ADE-R6") (pin "1") (pinfunction "1_1") (pintype "passive"))
      (node (ref "ETHERNET") (pin "4") (pinfunction "GND1_4") (pintype "bidirectional"))
      (node (ref "ETHERNET") (pin "5") (pinfunction "GND2_5") (pintype "bidirectional"))
      (node (ref "IC4") (pin "11") (pinfunction "AGND_11") (pintype "power_in"))
      (node (ref "STM-C9") (pin "2") (pinfunction "2_2") (pintype "passive"))
      (node (ref "STM_CHIP") (pin "12") (pinfunction "VSSA_12") (pintype "power_in"))
      (node (ref "SYS-C2") (pin "2") (pinfunction "2_2") (pintype "passive"))
      (node (ref "SYS-C4") (pin "2") (pinfunction "2_2") (pintype "passive"))
      (node (ref "SYS-L1") (pin "1") (pinfunction "1_1") (pintype "passive"))
    )
    (net (code "14") (name "CH1_A") (class "Default")
      (node (ref "JP1") (pin "2") (pinfunction "2_2") (pintype "passive"))
      (node (ref "OK2") (pin "8") (pinfunction "COL_8") (pintype "passive"))
    )
    (net (code "15") (name "CH1_B") (class "Default")
      (node (ref "JP1") (pin "1") (pinfunction "1_1") (pintype "passive"))
      (node (ref "OK2") (pin "7") (pinfunction "EMIT_7") (pintype "passive"))
    )
    (net (code "16") (name "CH1_IN") (class "Default")
      (node (ref "IC5") (pin "15") (pinfunction "QA_15") (pintype "tri_state"))
      (node (ref "OK2") (pin "2") (pinfunction "C_2") (pintype "passive"))
    )
    (net (code "17") (name "CH2_A") (class "Default")
      (node (ref "JP1") (pin "4") (pinfunction "4_4") (pintype "passive"))
      (node (ref "OK2") (pin "6") (pinfunction "COL_6") (pintype "passive"))
    )
    (net (code "18") (name "CH2_B") (class "Default")
      (node (ref "JP1") (pin "3") (pinfunction "3_3") (pintype "passive"))
      (node (ref "OK2") (pin "5") (pinfunction "EMIT_5") (pintype "passive"))
    )
    (net (code "19") (name "CH2_IN") (class "Default")
      (node (ref "IC5") (pin "1") (pinfunction "QB_1") (pintype "tri_state"))
      (node (ref "OK2") (pin "4") (pinfunction "C_4") (pintype "passive"))
    )
    (net (code "20") (name "CH3_A") (class "Default")
      (node (ref "JP1") (pin "6") (pinfunction "6_6") (pintype "passive"))
      (node (ref "OK1") (pin "8") (pinfunction "COL_8") (pintype "passive"))
    )
    (net (code "21") (name "CH3_B") (class "Default")
      (node (ref "JP1") (pin "5") (pinfunction "5_5") (pintype "passive"))
      (node (ref "OK1") (pin "7") (pinfunction "EMIT_7") (pintype "passive"))
    )
    (net (code "22") (name "CH3_IN") (class "Default")
      (node (ref "IC5") (pin "2") (pinfunction "QC_2") (pintype "tri_state"))
      (node (ref "OK1") (pin "2") (pinfunction "C_2") (pintype "passive"))
    )
    (net (code "23") (name "CH4_A") (class "Default")
      (node (ref "JP1") (pin "8") (pinfunction "8_8") (pintype "passive"))
      (node (ref "OK1") (pin "6") (pinfunction "COL_6") (pintype "passive"))
    )
    (net (code "24") (name "CH4_B") (class "Default")
      (node (ref "JP1") (pin "7") (pinfunction "7_7") (pintype "passive"))
      (node (ref "OK1") (pin "5") (pinfunction "EMIT_5") (pintype "passive"))
    )
    (net (code "25") (name "CH4_IN") (class "Default")
      (node (ref "IC5") (pin "3") (pinfunction "QD_3") (pintype "tri_state"))
      (node (ref "OK1") (pin "4") (pinfunction "C_4") (pintype "passive"))
    )
    (net (code "26") (name "DC_VOUT") (class "Default")
      (node (ref "DCDC-3.5V") (pin "OUTP#1") (pinfunction "VOUT_OUTP#1") (pintype "bidirectional"))
      (node (ref "DCDC-3.5V") (pin "OUTP#2") (pinfunction "VOUT_OUTP#2") (pintype "bidirectional"))
      (node (ref "PWR-SWT") (pin "2") (pinfunction "2_2") (pintype "passive"))
    )
    (net (code "27") (name "DGND") (class "Default")
      (node (ref "ADE-C3") (pin "2") (pinfunction "2_2") (pintype "passive"))
      (node (ref "ADE-C4") (pin "2") (pinfunction "2_2") (pintype "passive"))
      (node (ref "ADE-C5") (pin "-") (pinfunction "-_-") (pintype "passive"))
      (node (ref "ADE-C6") (pin "2") (pinfunction "2_2") (pintype "passive"))
      (node (ref "BAT1") (pin "2") (pinfunction "-_2") (pintype "power_in"))
      (node (ref "DCDC-3.5V") (pin "INM#1") (pinfunction "GNDI_INM#1") (pintype "bidirectional"))
      (node (ref "DCDC-3.5V") (pin "INM#2") (pinfunction "GNDI_INM#2") (pintype "bidirectional"))
      (node (ref "DCDC-3.5V") (pin "OUTM#1") (pinfunction "GNDO_OUTM#1") (pintype "bidirectional"))
      (node (ref "DCDC-3.5V") (pin "OUTM#2") (pinfunction "GNDO_OUTM#2") (pintype "bidirectional"))
      (node (ref "ESP-GND") (pin "1") (pinfunction "1_1") (pintype "passive"))
      (node (ref "ETH-C1") (pin "1") (pinfunction "1_1") (pintype "passive"))
      (node (ref "ETH-C3") (pin "1") (pinfunction "1_1") (pintype "passive"))
      (node (ref "IC1") (pin "P$17") (pinfunction "GND_P$17") (pintype "power_in"))
      (node (ref "IC1") (pin "P$18") (pinfunction "GND_P$18") (pintype "power_in"))
      (node (ref "IC1") (pin "P$29") (pinfunction "GND_P$29") (pintype "power_in"))
      (node (ref "IC1") (pin "P$39") (pinfunction "GND_P$39") (pintype "power_in"))
      (node (ref "IC1") (pin "P$45") (pinfunction "GND_P$45") (pintype "power_in"))
      (node (ref "IC1") (pin "P$46") (pinfunction "GND_P$46") (pintype "power_in"))
      (node (ref "IC1") (pin "P$53") (pinfunction "GND_P$53") (pintype "power_in"))
      (node (ref "IC1") (pin "P$54") (pinfunction "GND_P$54") (pintype "power_in"))
      (node (ref "IC1") (pin "P$58") (pinfunction "GND_P$58") (pintype "power_in"))
      (node (ref "IC1") (pin "P$59") (pinfunction "GND_P$59") (pintype "power_in"))
      (node (ref "IC1") (pin "P$61") (pinfunction "GND_P$61") (pintype "power_in"))
      (node (ref "IC1") (pin "P$62") (pinfunction "GND_P$62") (pintype "power_in"))
      (node (ref "IC1") (pin "P$63") (pinfunction "GND_P$63") (pintype "power_in"))
      (node (ref "IC1") (pin "P$64") (pinfunction "GND_P$64") (pintype "power_in"))
      (node (ref "IC1") (pin "P$65") (pinfunction "GND_P$65") (pintype "power_in"))
      (node (ref "IC2") (pin "13") (pinfunction "G_13") (pintype "input"))
      (node (ref "IC2") (pin "8") (pinfunction "GND_8") (pintype "power_in"))
      (node (ref "IC3") (pin "13") (pinfunction "G_13") (pintype "input"))
      (node (ref "IC3") (pin "8") (pinfunction "GND_8") (pintype "power_in"))
      (node (ref "IC4") (pin "2") (pinfunction "DGND_2") (pintype "power_in"))
      (node (ref "IC5") (pin "13") (pinfunction "G_13") (pintype "input"))
      (node (ref "IC5") (pin "8") (pinfunction "GND_8") (pintype "power_in"))
      (node (ref "J5") (pin "GND") (pinfunction "GND_GND") (pintype "bidirectional"))
      (node (ref "J5") (pin "GNDBREAK") (pinfunction "GNDBREAK_GNDBREAK") (pintype "bidirectional"))
      (node (ref "MQ6-R1") (pin "1") (pinfunction "1_1") (pintype "passive"))
      (node (ref "MQ7-R1") (pin "1") (pinfunction "1_1") (pintype "passive"))
      (node (ref "S1") (pin "3") (pinfunction "3_3") (pintype "passive"))
      (node (ref "S1") (pin "4") (pinfunction "4_4") (pintype "passive"))
      (node (ref "SENSOR-DHT") (pin "4") (pinfunction "4_4") (pintype "passive"))
      (node (ref "SENSOR-MQ6") (pin "HB") (pinfunction "HB_HB") (pintype "bidirectional"))
      (node (ref "SENSOR-MQ7") (pin "HB") (pinfunction "HB_HB") (pintype "bidirectional"))
      (node (ref "SIM900-ANT") (pin "GND1") (pinfunction "GND1_GND1") (pintype "power_in"))
      (node (ref "SIM900-ANT") (pin "GND2") (pinfunction "GND2_GND2") (pintype "power_in"))
      (node (ref "SIM900-ANT") (pin "GND3") (pinfunction "GND3_GND3") (pintype "power_in"))
      (node (ref "SIM900-ANT") (pin "GND4") (pinfunction "GND4_GND4") (pintype "power_in"))
      (node (ref "SIM900-C1") (pin "-") (pinfunction "-_-") (pintype "passive"))
      (node (ref "SIM900-C2") (pin "-") (pinfunction "-_-") (pintype "passive"))
      (node (ref "SIM900-C3") (pin "2") (pinfunction "2_2") (pintype "passive"))
      (node (ref "SIM900-C4") (pin "2") (pinfunction "2_2") (pintype "passive"))
      (node (ref "SIM900-C5") (pin "2") (pinfunction "2_2") (pintype "passive"))
      (node (ref "SIM900-R6") (pin "2") (pinfunction "2_2") (pintype "passive"))
      (node (ref "SIM900-R9") (pin "2") (pinfunction "2_2") (pintype "passive"))
      (node (ref "SIM900-T1") (pin "E") (pinfunction "E_E") (pintype "passive"))
      (node (ref "SIM900-T2") (pin "E") (pinfunction "E_E") (pintype "passive"))
      (node (ref "SIM900-T3") (pin "E") (pinfunction "E_E") (pintype "passive"))
      (node (ref "SIM900-T4") (pin "E") (pinfunction "E_E") (pintype "passive"))
      (node (ref "SIM_C1") (pin "1") (pinfunction "1_1") (pintype "passive"))
      (node (ref "SIM_C2") (pin "1") (pinfunction "1_1") (pintype "passive"))
      (node (ref "SIM_HOLDER") (pin "6") (pinfunction "GND_6") (pintype "bidirectional"))
      (node (ref "SR_OUT1") (pin "2") (pinfunction "2_2") (pintype "passive"))
      (node (ref "SR_OUT2") (pin "2") (pinfunction "2_2") (pintype "passive"))
      (node (ref "STM-C1") (pin "1") (pinfunction "1_1") (pintype "passive"))
      (node (ref "STM-C10") (pin "2") (pinfunction "2_2") (pintype "passive"))
      (node (ref "STM-C11") (pin "2") (pinfunction "2_2") (pintype "passive"))
      (node (ref "STM-C12") (pin "2") (pinfunction "2_2") (pintype "passive"))
      (node (ref "STM-C13") (pin "2") (pinfunction "2_2") (pintype "passive"))
      (node (ref "STM-C2") (pin "1") (pinfunction "1_1") (pintype "passive"))
      (node (ref "STM-C3") (pin "1") (pinfunction "1_1") (pintype "passive"))
      (node (ref "STM-C8") (pin "2") (pinfunction "2_2") (pintype "passive"))
      (node (ref "STM-SWD") (pin "3") (pinfunction "3_3") (pintype "passive"))
      (node (ref "STM-USART") (pin "4") (pinfunction "4_4") (pintype "passive"))
      (node (ref "STM_CHIP") (pin "18") (pinfunction "VSS_4_18") (pintype "power_in"))
      (node (ref "STM_CHIP") (pin "31") (pinfunction "VSS_1_31") (pintype "power_in"))
      (node (ref "STM_CHIP") (pin "47") (pinfunction "VSS_2_47") (pintype "power_in"))
      (node (ref "STM_CHIP") (pin "63") (pinfunction "VSS_3_63") (pintype "power_in"))
      (node (ref "SYS-C1") (pin "2") (pinfunction "2_2") (pintype "passive"))
      (node (ref "SYS-C3") (pin "2") (pinfunction "2_2") (pintype "passive"))
      (node (ref "SYS-L1") (pin "2") (pinfunction "2_2") (pintype "passive"))
      (node (ref "U$4") (pin "LCD_GND") (pinfunction "LCD_GND_LCD_GND") (pintype "passive"))
      (node (ref "U$6") (pin "1") (pinfunction "2_1") (pintype "passive"))
      (node (ref "U2") (pin "14") (pinfunction "AGND_14") (pintype "passive"))
      (node (ref "U2") (pin "16") (pinfunction "AGND_16") (pintype "passive"))
      (node (ref "U2") (pin "19") (pinfunction "AGND_19") (pintype "passive"))
      (node (ref "U2") (pin "29") (pinfunction "GND_29") (pintype "passive"))
      (node (ref "U2") (pin "3") (pinfunction "AGND_3") (pintype "passive"))
      (node (ref "U2") (pin "48") (pinfunction "AGND_48") (pintype "passive"))
      (node (ref "U2") (pin "9") (pinfunction "AGND_9") (pintype "passive"))
      (node (ref "W5500-C1") (pin "2") (pinfunction "2_2") (pintype "passive"))
      (node (ref "W5500-C10") (pin "2") (pinfunction "2_2") (pintype "passive"))
      (node (ref "W5500-C11") (pin "2") (pinfunction "2_2") (pintype "passive"))
      (node (ref "W5500-C12") (pin "-") (pinfunction "-_-") (pintype "passive"))
      (node (ref "W5500-C13") (pin "-") (pinfunction "-_-") (pintype "passive"))
      (node (ref "W5500-C2") (pin "2") (pinfunction "2_2") (pintype "passive"))
      (node (ref "W5500-C3") (pin "2") (pinfunction "2_2") (pintype "passive"))
      (node (ref "W5500-C4") (pin "2") (pinfunction "2_2") (pintype "passive"))
      (node (ref "W5500-C5") (pin "2") (pinfunction "2_2") (pintype "passive"))
      (node (ref "W5500-C6") (pin "2") (pinfunction "2_2") (pintype "passive"))
      (node (ref "W5500-C7") (pin "2") (pinfunction "2_2") (pintype "passive"))
      (node (ref "W5500-C8") (pin "2") (pinfunction "2_2") (pintype "passive"))
      (node (ref "W5500-C9") (pin "2") (pinfunction "2_2") (pintype "passive"))
      (node (ref "W5500-R11") (pin "1") (pinfunction "1_1") (pintype "passive"))
      (node (ref "W5500-R12") (pin "1") (pinfunction "1_1") (pintype "passive"))
      (node (ref "W5500-R4") (pin "2") (pinfunction "2_2") (pintype "passive"))
      (node (ref "W5500-R5") (pin "2") (pinfunction "2_2") (pintype "passive"))
      (node (ref "W5500-R6") (pin "2") (pinfunction "2_2") (pintype "passive"))
      (node (ref "W5500-R7") (pin "2") (pinfunction "2_2") (pintype "passive"))
      (node (ref "W5500-R8") (pin "2") (pinfunction "2_2") (pintype "passive"))
    )
    (net (code "28") (name "DHT_DATA") (class "Default")
      (node (ref "DHT-R1") (pin "2") (pinfunction "2_2") (pintype "passive"))
      (node (ref "SENSOR-DHT") (pin "2") (pinfunction "2_2") (pintype "passive"))
      (node (ref "STM_CHIP") (pin "15") (pinfunction "PA1_15") (pintype "bidirectional"))
    )
    (net (code "29") (name "ESP_GPIO0") (class "Default")
      (node (ref "ESP-GPIO0") (pin "2") (pinfunction "2_2") (pintype "passive"))
      (node (ref "U$5") (pin "GPIO00") (pinfunction "GPIO0_GPIO00") (pintype "bidirectional"))
    )
    (net (code "30") (name "ESP_RX") (class "Default")
      (node (ref "ESP-UART-A") (pin "2") (pinfunction "2_2") (pintype "passive"))
      (node (ref "JP_ESP_RX") (pin "1") (pinfunction "1_1") (pintype "passive"))
      (node (ref "U$5") (pin "RXD") (pinfunction "RXD_RXD") (pintype "bidirectional"))
    )
    (net (code "31") (name "ESP_TX") (class "Default")
      (node (ref "ESP-UART-A") (pin "3") (pinfunction "3_3") (pintype "passive"))
      (node (ref "JP_ESP_TX") (pin "1") (pinfunction "1_1") (pintype "passive"))
      (node (ref "U$5") (pin "TXD") (pinfunction "TXD_TXD") (pintype "bidirectional"))
    )
    (net (code "32") (name "ETH_CS") (class "Default")
      (node (ref "STM_CHIP") (pin "33") (pinfunction "PB12_33") (pintype "bidirectional"))
      (node (ref "U2") (pin "32") (pinfunction "SCS_N_32") (pintype "passive"))
      (node (ref "W5500-R13") (pin "1") (pinfunction "1_1") (pintype "passive"))
    )
    (net (code "33") (name "ETH_MISO") (class "Default")
      (node (ref "STM_CHIP") (pin "35") (pinfunction "PB14_35") (pintype "bidirectional"))
      (node (ref "U2") (pin "34") (pinfunction "MISO_34") (pintype "passive"))
    )
    (net (code "34") (name "ETH_MOSI") (class "Default")
      (node (ref "STM_CHIP") (pin "36") (pinfunction "PB15_36") (pintype "bidirectional"))
      (node (ref "U2") (pin "35") (pinfunction "MOSI_35") (pintype "passive"))
    )
    (net (code "35") (name "ETH_RSTN") (class "Default")
      (node (ref "STM_CHIP") (pin "37") (pinfunction "PC6_37") (pintype "bidirectional"))
      (node (ref "U2") (pin "37") (pinfunction "RST_N_37") (pintype "passive"))
      (node (ref "W5500-R9") (pin "1") (pinfunction "1_1") (pintype "passive"))
    )
    (net (code "36") (name "ETH_SCK") (class "Default")
      (node (ref "STM_CHIP") (pin "34") (pinfunction "PB13_34") (pintype "bidirectional"))
      (node (ref "U2") (pin "33") (pinfunction "SCLK_33") (pintype "passive"))
    )
    (net (code "37") (name "F_CS") (class "Default")
      (node (ref "STM_CHIP") (pin "29") (pinfunction "PB10_29") (pintype "bidirectional"))
      (node (ref "U$4") (pin "F_CS") (pinfunction "F_CS_F_CS") (pintype "passive"))
    )
    (net (code "38") (name "GESP") (class "Default")
      (node (ref "ESP-C1") (pin "2") (pinfunction "2_2") (pintype "passive"))
      (node (ref "ESP-GND") (pin "2") (pinfunction "2_2") (pintype "passive"))
      (node (ref "ESP-GPIO0") (pin "3") (pinfunction "3_3") (pintype "passive"))
      (node (ref "U$5") (pin "GND") (pinfunction "GND_GND") (pintype "bidirectional"))
      (node (ref "U$5") (pin "GPIO15") (pinfunction "GPIO15_GPIO15") (pintype "bidirectional"))
    )
    (net (code "39") (name "GEXT") (class "Default")
      (node (ref "ESP-GND") (pin "3") (pinfunction "3_3") (pintype "passive"))
      (node (ref "ESP-UART-A") (pin "4") (pinfunction "4_4") (pintype "passive"))
    )
    (net (code "40") (name "LCD_CS") (class "Default")
      (node (ref "STM_CHIP") (pin "20") (pinfunction "PA4_20") (pintype "bidirectional"))
      (node (ref "U$4") (pin "LCD_CS") (pinfunction "LCD_CS_LCD_CS") (pintype "passive"))
    )
    (net (code "41") (name "LCD_D{slash}C") (class "Default")
      (node (ref "STM_CHIP") (pin "24") (pinfunction "PC4_24") (pintype "bidirectional"))
      (node (ref "U$4") (pin "LCD_D/C") (pinfunction "LCD_D/C_LCD_D/C") (pintype "passive"))
    )
    (net (code "42") (name "LCD_LED") (class "Default")
      (node (ref "LCD-R1") (pin "1") (pinfunction "1_1") (pintype "passive"))
      (node (ref "U$4") (pin "LCD_LED") (pinfunction "LCD_LED_LCD_LED") (pintype "passive"))
    )
    (net (code "43") (name "LCD_MISO") (class "Default")
      (node (ref "STM_CHIP") (pin "22") (pinfunction "PA6_22") (pintype "bidirectional"))
      (node (ref "U$4") (pin "LCD_MISO") (pinfunction "LCD_MISO_LCD_MISO") (pintype "passive"))
      (node (ref "U$4") (pin "SD_MISO") (pinfunction "SD_MISO_SD_MISO") (pintype "passive"))
    )
    (net (code "44") (name "LCD_MOSI") (class "Default")
      (node (ref "STM_CHIP") (pin "23") (pinfunction "PA7_23") (pintype "bidirectional"))
      (node (ref "U$4") (pin "LCD_MOSI") (pinfunction "LCD_MOSI_LCD_MOSI") (pintype "passive"))
      (node (ref "U$4") (pin "SD_MOSI") (pinfunction "SD_MOSI_SD_MOSI") (pintype "passive"))
    )
    (net (code "45") (name "LCD_RESET") (class "Default")
      (node (ref "STM_CHIP") (pin "25") (pinfunction "PC5_25") (pintype "bidirectional"))
      (node (ref "U$4") (pin "LCD_RESET") (pinfunction "LCD_RESET_LCD_RESET") (pintype "passive"))
    )
    (net (code "46") (name "LCD_SCK") (class "Default")
      (node (ref "STM_CHIP") (pin "21") (pinfunction "PA5_21") (pintype "bidirectional"))
      (node (ref "U$4") (pin "LCD_SCK") (pinfunction "LCD_SCK_LCD_SCK") (pintype "passive"))
      (node (ref "U$4") (pin "SD_SCK") (pinfunction "SD_SCK_SD_SCK") (pintype "passive"))
    )
    (net (code "47") (name "LINKLED") (class "Default")
      (node (ref "ETH-R5") (pin "1") (pinfunction "1_1") (pintype "passive"))
      (node (ref "U2") (pin "25") (pinfunction "LINKLED_25") (pintype "passive"))
    )
    (net (code "48") (name "MQ6_DATA") (class "Default")
      (node (ref "SENSOR-MQ7") (pin "B1") (pinfunction "B1_B1") (pintype "bidirectional"))
      (node (ref "STM_CHIP") (pin "26") (pinfunction "PB0_26") (pintype "bidirectional"))
    )
    (net (code "49") (name "MQ7_DATA") (class "Default")
      (node (ref "SENSOR-MQ6") (pin "B1") (pinfunction "B1_B1") (pintype "bidirectional"))
      (node (ref "STM_CHIP") (pin "27") (pinfunction "PB1_27") (pintype "bidirectional"))
    )
    (net (code "50") (name "Net-(ADE-R1-Pad1)") (class "Default")
      (node (ref "ADE-R1") (pin "1") (pinfunction "1_1") (pintype "passive"))
      (node (ref "VAC_IN1") (pin "PWR") (pinfunction "PWR_PWR") (pintype "bidirectional"))
    )
    (net (code "51") (name "Net-(ADE-R2-Pad1)") (class "Default")
      (node (ref "ADE-R2") (pin "1") (pinfunction "1_1") (pintype "passive"))
      (node (ref "VAC_IN2") (pin "PWR") (pinfunction "PWR_PWR") (pintype "bidirectional"))
    )
    (net (code "52") (name "Net-(ADE-R3-Pad1)") (class "Default")
      (node (ref "ADE-R3") (pin "1") (pinfunction "1_1") (pintype "passive"))
      (node (ref "VAC_IN3") (pin "PWR") (pinfunction "PWR_PWR") (pintype "bidirectional"))
    )
    (net (code "53") (name "Net-(ADE-R7-Pad1)") (class "Default")
      (node (ref "ADE-R7") (pin "1") (pinfunction "1_1") (pintype "passive"))
      (node (ref "VAC_IN1") (pin "GND") (pinfunction "GND_GND") (pintype "bidirectional"))
      (node (ref "VAC_IN1") (pin "GNDBREAK") (pinfunction "GNDBREAK_GNDBREAK") (pintype "bidirectional"))
      (node (ref "VAC_IN2") (pin "GND") (pinfunction "GND_GND") (pintype "bidirectional"))
      (node (ref "VAC_IN2") (pin "GNDBREAK") (pinfunction "GNDBREAK_GNDBREAK") (pintype "bidirectional"))
      (node (ref "VAC_IN3") (pin "GND") (pinfunction "GND_GND") (pintype "bidirectional"))
      (node (ref "VAC_IN3") (pin "GNDBREAK") (pinfunction "GNDBREAK_GNDBREAK") (pintype "bidirectional"))
    )
    (net (code "54") (name "Net-(ADE-R8-Pad2)") (class "Default")
      (node (ref "ADE-R8") (pin "2") (pinfunction "2_2") (pintype "passive"))
      (node (ref "ADE-R9") (pin "1") (pinfunction "1_1") (pintype "passive"))
      (node (ref "CT1") (pin "1") (pinfunction "1_1") (pintype "passive"))
    )
    (net (code "55") (name "Net-(ADE-R10-Pad1)") (class "Default")
      (node (ref "ADE-R10") (pin "1") (pinfunction "1_1") (pintype "passive"))
      (node (ref "ADE-R8") (pin "1") (pinfunction "1_1") (pintype "passive"))
      (node (ref "CT1") (pin "2") (pinfunction "2_2") (pintype "passive"))
      (node (ref "CT1") (pin "5") (pinfunction "5_5") (pintype "passive"))
    )
    (net (code "56") (name "Net-(ADE-R11-Pad1)") (class "Default")
      (node (ref "ADE-R11") (pin "1") (pinfunction "1_1") (pintype "passive"))
      (node (ref "ADE-R13") (pin "1") (pinfunction "1_1") (pintype "passive"))
      (node (ref "CT2") (pin "2") (pinfunction "2_2") (pintype "passive"))
      (node (ref "CT2") (pin "5") (pinfunction "5_5") (pintype "passive"))
    )
    (net (code "57") (name "Net-(ADE-R11-Pad2)") (class "Default")
      (node (ref "ADE-R11") (pin "2") (pinfunction "2_2") (pintype "passive"))
      (node (ref "ADE-R12") (pin "1") (pinfunction "1_1") (pintype "passive"))
      (node (ref "CT2") (pin "1") (pinfunction "1_1") (pintype "passive"))
    )
    (net (code "58") (name "Net-(ADE-R14-Pad1)") (class "Default")
      (node (ref "ADE-R14") (pin "1") (pinfunction "1_1") (pintype "passive"))
      (node (ref "ADE-R16") (pin "1") (pinfunction "1_1") (pintype "passive"))
      (node (ref "CT3") (pin "2") (pinfunction "2_2") (pintype "passive"))
      (node (ref "CT3") (pin "5") (pinfunction "5_5") (pintype "passive"))
    )
    (net (code "59") (name "Net-(ADE-R14-Pad2)") (class "Default")
      (node (ref "ADE-R14") (pin "2") (pinfunction "2_2") (pintype "passive"))
      (node (ref "ADE-R15") (pin "1") (pinfunction "1_1") (pintype "passive"))
      (node (ref "CT3") (pin "1") (pinfunction "1_1") (pintype "passive"))
    )
    (net (code "60") (name "Net-(ETHERNET-LED1_K)") (class "Default")
      (node (ref "ETH-R4") (pin "2") (pinfunction "2_2") (pintype "passive"))
      (node (ref "ETHERNET") (pin "10") (pinfunction "LED1_K_10") (pintype "bidirectional"))
    )
    (net (code "61") (name "Net-(ETHERNET-LED2_K)") (class "Default")
      (node (ref "ETH-R5") (pin "2") (pinfunction "2_2") (pintype "passive"))
      (node (ref "ETHERNET") (pin "11") (pinfunction "LED2_K_11") (pintype "bidirectional"))
    )
    (net (code "62") (name "Net-(ETHERNET-RCT)") (class "Default")
      (node (ref "ETH-C3") (pin "2") (pinfunction "2_2") (pintype "passive"))
      (node (ref "ETH-R6") (pin "1") (pinfunction "1_1") (pintype "passive"))
      (node (ref "ETH-R7") (pin "2") (pinfunction "2_2") (pintype "passive"))
      (node (ref "ETHERNET") (pin "6") (pinfunction "RCT_6") (pintype "bidirectional"))
    )
    (net (code "63") (name "Net-(ETHERNET-RX+)") (class "Default")
      (node (ref "ETH-C2") (pin "1") (pinfunction "1_1") (pintype "passive"))
      (node (ref "ETHERNET") (pin "7") (pinfunction "RX+_7") (pintype "bidirectional"))
    )
    (net (code "64") (name "Net-(ETHERNET-RX-)") (class "Default")
      (node (ref "ETH-C4") (pin "1") (pinfunction "1_1") (pintype "passive"))
      (node (ref "ETHERNET") (pin "8") (pinfunction "RX-_8") (pintype "bidirectional"))
    )
    (net (code "65") (name "Net-(ETHERNET-TCT)") (class "Default")
      (node (ref "ETH-C1") (pin "2") (pinfunction "2_2") (pintype "passive"))
      (node (ref "ETH-R3") (pin "1") (pinfunction "1_1") (pintype "passive"))
      (node (ref "ETHERNET") (pin "3") (pinfunction "TCT_3") (pintype "bidirectional"))
    )
    (net (code "66") (name "Net-(IC1-RF_ANT)") (class "Default")
      (node (ref "IC1") (pin "P$60") (pinfunction "RF_ANT_P$60") (pintype "bidirectional"))
      (node (ref "SIM900-ANT") (pin "ANTENNA") (pinfunction "ANT_ANTENNA") (pintype "bidirectional"))
    )
    (net (code "67") (name "Net-(IC1-SIM_CLK)") (class "Default")
      (node (ref "IC1") (pin "P$32") (pinfunction "SIM_CLK_P$32") (pintype "bidirectional"))
      (node (ref "SIM900-R2") (pin "1") (pinfunction "1_1") (pintype "passive"))
    )
    (net (code "68") (name "Net-(IC1-SIM_DATA)") (class "Default")
      (node (ref "IC1") (pin "P$31") (pinfunction "SIM_DATA_P$31") (pintype "bidirectional"))
      (node (ref "SIM900-R3") (pin "1") (pinfunction "1_1") (pintype "passive"))
    )
    (net (code "69") (name "Net-(IC1-SIM_RST)") (class "Default")
      (node (ref "IC1") (pin "P$33") (pinfunction "SIM_RST_P$33") (pintype "bidirectional"))
      (node (ref "SIM900-R1") (pin "1") (pinfunction "1_1") (pintype "passive"))
    )
    (net (code "70") (name "Net-(IC1-VBAT1)") (class "Default")
      (node (ref "IC1") (pin "P$55") (pinfunction "VBAT1_P$55") (pintype "power_in"))
      (node (ref "IC1") (pin "P$56") (pinfunction "VBAT2_P$56") (pintype "power_in"))
      (node (ref "IC1") (pin "P$57") (pinfunction "VBAT3_P$57") (pintype "power_in"))
      (node (ref "SIM900-C1") (pin "+") (pinfunction "+_+") (pintype "passive"))
      (node (ref "SIM900-C2") (pin "+") (pinfunction "+_+") (pintype "passive"))
      (node (ref "SYS-L2") (pin "1") (pinfunction "1_1") (pintype "passive"))
    )
    (net (code "71") (name "Net-(IC1-VRTC)") (class "Default")
      (node (ref "IC1") (pin "P$26") (pinfunction "VRTC_P$26") (pintype "power_in"))
      (node (ref "SIM900-C3") (pin "1") (pinfunction "1_1") (pintype "passive"))
    )
    (net (code "72") (name "Net-(IC4A-CLKIN)") (class "Default")
      (node (ref "ADE-C3") (pin "1") (pinfunction "1_1") (pintype "passive"))
      (node (ref "ADE-XTAL") (pin "1") (pinfunction "1_1") (pintype "passive"))
      (node (ref "IC4") (pin "19") (pinfunction "CLKIN_19") (pintype "input"))
    )
    (net (code "73") (name "Net-(IC4A-CLKOUT)") (class "Default")
      (node (ref "ADE-C4") (pin "1") (pinfunction "1_1") (pintype "passive"))
      (node (ref "ADE-XTAL") (pin "2") (pinfunction "2_2") (pintype "passive"))
      (node (ref "IC4") (pin "20") (pinfunction "CLKOUT_20") (pintype "output"))
    )
    (net (code "74") (name "Net-(IC4C-IN)") (class "Default")
      (node (ref "ADE-C12") (pin "1") (pinfunction "1_1") (pintype "passive"))
      (node (ref "ADE-R10") (pin "2") (pinfunction "2_2") (pintype "passive"))
      (node (ref "IC4") (pin "6") (pinfunction "IN_6") (pintype "input"))
    )
    (net (code "75") (name "Net-(IC4C-IP)") (class "Default")
      (node (ref "ADE-C11") (pin "1") (pinfunction "1_1") (pintype "passive"))
      (node (ref "ADE-R9") (pin "2") (pinfunction "2_2") (pintype "passive"))
      (node (ref "IC4") (pin "5") (pinfunction "IP_5") (pintype "input"))
    )
    (net (code "76") (name "Net-(IC4D-IN)") (class "Default")
      (node (ref "ADE-C14") (pin "1") (pinfunction "1_1") (pintype "passive"))
      (node (ref "ADE-R13") (pin "2") (pinfunction "2_2") (pintype "passive"))
      (node (ref "IC4") (pin "8") (pinfunction "IN_8") (pintype "input"))
    )
    (net (code "77") (name "Net-(IC4D-IP)") (class "Default")
      (node (ref "ADE-C13") (pin "1") (pinfunction "1_1") (pintype "passive"))
      (node (ref "ADE-R12") (pin "2") (pinfunction "2_2") (pintype "passive"))
      (node (ref "IC4") (pin "7") (pinfunction "IP_7") (pintype "input"))
    )
    (net (code "78") (name "Net-(IC4E-IN)") (class "Default")
      (node (ref "ADE-C16") (pin "1") (pinfunction "1_1") (pintype "passive"))
      (node (ref "ADE-R16") (pin "2") (pinfunction "2_2") (pintype "passive"))
      (node (ref "IC4") (pin "10") (pinfunction "IN_10") (pintype "input"))
    )
    (net (code "79") (name "Net-(IC4E-IP)") (class "Default")
      (node (ref "ADE-C15") (pin "1") (pinfunction "1_1") (pintype "passive"))
      (node (ref "ADE-R15") (pin "2") (pinfunction "2_2") (pintype "passive"))
      (node (ref "IC4") (pin "9") (pinfunction "IP_9") (pintype "input"))
    )
    (net (code "80") (name "Net-(IC4F-REF)") (class "Default")
      (node (ref "ADE-C1") (pin "1") (pinfunction "1_1") (pintype "passive"))
      (node (ref "ADE-C2") (pin "1") (pinfunction "1_1") (pintype "passive"))
      (node (ref "IC4") (pin "12") (pinfunction "REF_12") (pintype "bidirectional"))
    )
    (net (code "81") (name "Net-(IC4G-VAP)") (class "Default")
      (node (ref "ADE-C7") (pin "1") (pinfunction "1_1") (pintype "passive"))
      (node (ref "ADE-R1") (pin "2") (pinfunction "2_2") (pintype "passive"))
      (node (ref "ADE-R4") (pin "2") (pinfunction "2_2") (pintype "passive"))
      (node (ref "IC4") (pin "16") (pinfunction "VAP_16") (pintype "input"))
    )
    (net (code "82") (name "Net-(IC4G-VBP)") (class "Default")
      (node (ref "ADE-C8") (pin "1") (pinfunction "1_1") (pintype "passive"))
      (node (ref "ADE-R2") (pin "2") (pinfunction "2_2") (pintype "passive"))
      (node (ref "ADE-R5") (pin "2") (pinfunction "2_2") (pintype "passive"))
      (node (ref "IC4") (pin "15") (pinfunction "VBP_15") (pintype "input"))
    )
    (net (code "83") (name "Net-(IC4G-VCP)") (class "Default")
      (node (ref "ADE-C9") (pin "1") (pinfunction "1_1") (pintype "passive"))
      (node (ref "ADE-R3") (pin "2") (pinfunction "2_2") (pintype "passive"))
      (node (ref "ADE-R6") (pin "2") (pinfunction "2_2") (pintype "passive"))
      (node (ref "IC4") (pin "14") (pinfunction "VCP_14") (pintype "input"))
    )
    (net (code "84") (name "Net-(IC4G-VN)") (class "Default")
      (node (ref "ADE-C10") (pin "1") (pinfunction "1_1") (pintype "passive"))
      (node (ref "ADE-R7") (pin "2") (pinfunction "2_2") (pintype "passive"))
      (node (ref "IC4") (pin "13") (pinfunction "VN_13") (pintype "input"))
    )
    (net (code "85") (name "Net-(LED1-PadA)") (class "Default")
      (node (ref "LED1") (pin "A") (pinfunction "A_A") (pintype "passive"))
      (node (ref "R1") (pin "2") (pinfunction "2_2") (pintype "passive"))
    )
    (net (code "86") (name "Net-(MQ6-R1-Pad2)") (class "Default")
      (node (ref "MQ6-R1") (pin "2") (pinfunction "2_2") (pintype "passive"))
      (node (ref "SENSOR-MQ6") (pin "B2") (pinfunction "B2_B2") (pintype "bidirectional"))
    )
    (net (code "87") (name "Net-(MQ7-R1-Pad2)") (class "Default")
      (node (ref "MQ7-R1") (pin "2") (pinfunction "2_2") (pintype "passive"))
      (node (ref "SENSOR-MQ7") (pin "B2") (pinfunction "B2_B2") (pintype "bidirectional"))
    )
    (net (code "88") (name "Net-(OK1A-A)") (class "Default")
      (node (ref "OK1") (pin "1") (pinfunction "A_1") (pintype "passive"))
      (node (ref "R_CH3") (pin "2") (pinfunction "2_2") (pintype "passive"))
    )
    (net (code "89") (name "Net-(OK1B-A)") (class "Default")
      (node (ref "OK1") (pin "3") (pinfunction "A_3") (pintype "passive"))
      (node (ref "R_CH4") (pin "2") (pinfunction "2_2") (pintype "passive"))
    )
    (net (code "90") (name "Net-(OK2A-A)") (class "Default")
      (node (ref "OK2") (pin "1") (pinfunction "A_1") (pintype "passive"))
      (node (ref "R_CH1") (pin "2") (pinfunction "2_2") (pintype "passive"))
    )
    (net (code "91") (name "Net-(OK2B-A)") (class "Default")
      (node (ref "OK2") (pin "3") (pinfunction "A_3") (pintype "passive"))
      (node (ref "R_CH2") (pin "2") (pinfunction "2_2") (pintype "passive"))
    )
    (net (code "92") (name "Net-(SIM900-LED1-PadA)") (class "Default")
      (node (ref "SIM900-LED1") (pin "A") (pinfunction "A_A") (pintype "passive"))
      (node (ref "SIM900-R4") (pin "1") (pinfunction "1_1") (pintype "passive"))
    )
    (net (code "93") (name "Net-(SIM900-LED1-PadC)") (class "Default")
      (node (ref "SIM900-LED1") (pin "C") (pinfunction "C_C") (pintype "passive"))
      (node (ref "SIM900-T1") (pin "C") (pinfunction "C_C") (pintype "passive"))
    )
    (net (code "94") (name "Net-(SIM900-LED2-PadA)") (class "Default")
      (node (ref "SIM900-LED2") (pin "A") (pinfunction "A_A") (pintype "passive"))
      (node (ref "SIM900-R7") (pin "1") (pinfunction "1_1") (pintype "passive"))
    )
    (net (code "95") (name "Net-(SIM900-LED2-PadC)") (class "Default")
      (node (ref "SIM900-LED2") (pin "C") (pinfunction "C_C") (pintype "passive"))
      (node (ref "SIM900-T2") (pin "C") (pinfunction "C_C") (pintype "passive"))
    )
    (net (code "96") (name "Net-(SIM900-R5-Pad1)") (class "Default")
      (node (ref "SIM900-R5") (pin "1") (pinfunction "1_1") (pintype "passive"))
      (node (ref "SIM900-R6") (pin "1") (pinfunction "1_1") (pintype "passive"))
      (node (ref "SIM900-T1") (pin "B") (pinfunction "B_B") (pintype "passive"))
    )
    (net (code "97") (name "Net-(SIM900-R8-Pad1)") (class "Default")
      (node (ref "SIM900-R8") (pin "1") (pinfunction "1_1") (pintype "passive"))
      (node (ref "SIM900-R9") (pin "1") (pinfunction "1_1") (pintype "passive"))
      (node (ref "SIM900-T2") (pin "B") (pinfunction "B_B") (pintype "passive"))
    )
    (net (code "98") (name "Net-(SIM900-R10-Pad2)") (class "Default")
      (node (ref "SIM900-R10") (pin "2") (pinfunction "2_2") (pintype "passive"))
      (node (ref "SIM900-T3") (pin "B") (pinfunction "B_B") (pintype "passive"))
    )
    (net (code "99") (name "Net-(SIM900-R11-Pad2)") (class "Default")
      (node (ref "SIM900-R11") (pin "2") (pinfunction "2_2") (pintype "passive"))
      (node (ref "SIM900-T4") (pin "B") (pinfunction "B_B") (pintype "passive"))
    )
    (net (code "100") (name "Net-(STM_CHIP-PA2)") (class "Default")
      (node (ref "JP_ESP_RX") (pin "2") (pinfunction "2_2") (pintype "passive"))
      (node (ref "STM_CHIP") (pin "16") (pinfunction "PA2_16") (pintype "bidirectional"))
    )
    (net (code "101") (name "Net-(STM_CHIP-PA3)") (class "Default")
      (node (ref "JP_ESP_TX") (pin "2") (pinfunction "2_2") (pintype "passive"))
      (node (ref "STM_CHIP") (pin "17") (pinfunction "PA3_17") (pintype "bidirectional"))
    )
    (net (code "102") (name "Net-(STM_CHIP-PC8)") (class "Default")
      (node (ref "LED1") (pin "C") (pinfunction "C_C") (pintype "passive"))
      (node (ref "STM_CHIP") (pin "39") (pinfunction "PC8_39") (pintype "bidirectional"))
    )
    (net (code "103") (name "Net-(STM_CHIP-PC14-OSC32_IN)") (class "Default")
      (node (ref "STM-C2") (pin "2") (pinfunction "2_2") (pintype "passive"))
      (node (ref "STM-XTAL") (pin "2") (pinfunction "2_2") (pintype "passive"))
      (node (ref "STM_CHIP") (pin "3") (pinfunction "PC14-OSC32_IN_3") (pintype "bidirectional"))
    )
    (net (code "104") (name "Net-(STM_CHIP-PC15-OSC32_OUT)") (class "Default")
      (node (ref "STM-C3") (pin "2") (pinfunction "2_2") (pintype "passive"))
      (node (ref "STM-XTAL") (pin "1") (pinfunction "1_1") (pintype "passive"))
      (node (ref "STM_CHIP") (pin "4") (pinfunction "PC15-OSC32_OUT_4") (pintype "bidirectional"))
    )
    (net (code "105") (name "Net-(U2-1V2O)") (class "Default")
      (node (ref "U2") (pin "22") (pinfunction "1V2O_22") (pintype "passive"))
      (node (ref "W5500-C4") (pin "1") (pinfunction "1_1") (pintype "passive"))
    )
    (net (code "106") (name "Net-(U2-EXRES1)") (class "Default")
      (node (ref "U2") (pin "10") (pinfunction "EXRES1_10") (pintype "passive"))
      (node (ref "W5500-R12") (pin "2") (pinfunction "2_2") (pintype "passive"))
    )
    (net (code "107") (name "Net-(U2-PMODE0)") (class "Default")
      (node (ref "U2") (pin "45") (pinfunction "PMODE0_45") (pintype "passive"))
      (node (ref "W5500-R3") (pin "2") (pinfunction "2_2") (pintype "passive"))
    )
    (net (code "108") (name "Net-(U2-PMODE1)") (class "Default")
      (node (ref "U2") (pin "44") (pinfunction "PMODE1_44") (pintype "passive"))
      (node (ref "W5500-R2") (pin "2") (pinfunction "2_2") (pintype "passive"))
    )
    (net (code "109") (name "Net-(U2-PMODE2)") (class "Default")
      (node (ref "U2") (pin "43") (pinfunction "PMODE2_43") (pintype "passive"))
      (node (ref "W5500-R1") (pin "2") (pinfunction "2_2") (pintype "passive"))
    )
    (net (code "110") (name "Net-(U2-RSVD-Pad23)") (class "Default")
      (node (ref "U2") (pin "23") (pinfunction "RSVD_23") (pintype "passive"))
      (node (ref "W5500-R11") (pin "2") (pinfunction "2_2") (pintype "passive"))
    )
    (net (code "111") (name "Net-(U2-RSVD-Pad38)") (class "Default")
      (node (ref "U2") (pin "38") (pinfunction "RSVD_38") (pintype "passive"))
      (node (ref "W5500-R8") (pin "1") (pinfunction "1_1") (pintype "passive"))
    )
    (net (code "112") (name "Net-(U2-RSVD-Pad39)") (class "Default")
      (node (ref "U2") (pin "39") (pinfunction "RSVD_39") (pintype "passive"))
      (node (ref "W5500-R7") (pin "1") (pinfunction "1_1") (pintype "passive"))
    )
    (net (code "113") (name "Net-(U2-RSVD-Pad40)") (class "Default")
      (node (ref "U2") (pin "40") (pinfunction "RSVD_40") (pintype "passive"))
      (node (ref "W5500-R6") (pin "1") (pinfunction "1_1") (pintype "passive"))
    )
    (net (code "114") (name "Net-(U2-RSVD-Pad41)") (class "Default")
      (node (ref "U2") (pin "41") (pinfunction "RSVD_41") (pintype "passive"))
      (node (ref "W5500-R5") (pin "1") (pinfunction "1_1") (pintype "passive"))
    )
    (net (code "115") (name "Net-(U2-RSVD-Pad42)") (class "Default")
      (node (ref "U2") (pin "42") (pinfunction "RSVD_42") (pintype "passive"))
      (node (ref "W5500-R4") (pin "1") (pinfunction "1_1") (pintype "passive"))
    )
    (net (code "116") (name "Net-(U2-TOCAP)") (class "Default")
      (node (ref "U2") (pin "20") (pinfunction "TOCAP_20") (pintype "passive"))
      (node (ref "W5500-C3") (pin "1") (pinfunction "1_1") (pintype "passive"))
    )
    (net (code "117") (name "Net-(U2-XI{slash}CLKIN)") (class "Default")
      (node (ref "U$3") (pin "P$1") (pinfunction "P$1_P$1") (pintype "bidirectional"))
      (node (ref "U2") (pin "30") (pinfunction "XI/CLKIN_30") (pintype "passive"))
      (node (ref "W5500-C1") (pin "1") (pinfunction "1_1") (pintype "passive"))
      (node (ref "W5500-R10") (pin "1") (pinfunction "1_1") (pintype "passive"))
      (node (ref "W5500-XTAL") (pin "1") (pinfunction "1_1") (pintype "passive"))
    )
    (net (code "118") (name "Net-(U2-XO)") (class "Default")
      (node (ref "U$3") (pin "P$2") (pinfunction "P$2_P$2") (pintype "bidirectional"))
      (node (ref "U2") (pin "31") (pinfunction "XO_31") (pintype "passive"))
      (node (ref "W5500-C2") (pin "1") (pinfunction "1_1") (pintype "passive"))
      (node (ref "W5500-R10") (pin "2") (pinfunction "2_2") (pintype "passive"))
      (node (ref "W5500-XTAL") (pin "2") (pinfunction "2_2") (pintype "passive"))
    )
    (net (code "119") (name "Q1") (class "Default")
      (node (ref "IC2") (pin "15") (pinfunction "QA_15") (pintype "tri_state"))
      (node (ref "SR_OUT1") (pin "3") (pinfunction "3_3") (pintype "passive"))
    )
    (net (code "120") (name "Q2") (class "Default")
      (node (ref "IC2") (pin "1") (pinfunction "QB_1") (pintype "tri_state"))
      (node (ref "SR_OUT1") (pin "4") (pinfunction "4_4") (pintype "passive"))
    )
    (net (code "121") (name "Q3") (class "Default")
      (node (ref "IC2") (pin "2") (pinfunction "QC_2") (pintype "tri_state"))
      (node (ref "SR_OUT1") (pin "5") (pinfunction "5_5") (pintype "passive"))
    )
    (net (code "122") (name "Q4") (class "Default")
      (node (ref "IC2") (pin "3") (pinfunction "QD_3") (pintype "tri_state"))
      (node (ref "SR_OUT1") (pin "6") (pinfunction "6_6") (pintype "passive"))
    )
    (net (code "123") (name "Q5") (class "Default")
      (node (ref "IC2") (pin "4") (pinfunction "QE_4") (pintype "tri_state"))
      (node (ref "SR_OUT1") (pin "7") (pinfunction "7_7") (pintype "passive"))
    )
    (net (code "124") (name "Q6") (class "Default")
      (node (ref "IC2") (pin "5") (pinfunction "QF_5") (pintype "tri_state"))
      (node (ref "SR_OUT1") (pin "8") (pinfunction "8_8") (pintype "passive"))
    )
    (net (code "125") (name "Q7") (class "Default")
      (node (ref "IC2") (pin "6") (pinfunction "QG_6") (pintype "tri_state"))
      (node (ref "SR_OUT1") (pin "9") (pinfunction "9_9") (pintype "passive"))
    )
    (net (code "126") (name "Q8") (class "Default")
      (node (ref "IC2") (pin "7") (pinfunction "QH_7") (pintype "tri_state"))
      (node (ref "SR_OUT1") (pin "10") (pinfunction "10_10") (pintype "passive"))
    )
    (net (code "127") (name "Q9") (class "Default")
      (node (ref "IC3") (pin "15") (pinfunction "QA_15") (pintype "tri_state"))
      (node (ref "SR_OUT2") (pin "3") (pinfunction "3_3") (pintype "passive"))
    )
    (net (code "128") (name "Q10") (class "Default")
      (node (ref "IC3") (pin "1") (pinfunction "QB_1") (pintype "tri_state"))
      (node (ref "SR_OUT2") (pin "4") (pinfunction "4_4") (pintype "passive"))
    )
    (net (code "129") (name "Q11") (class "Default")
      (node (ref "IC3") (pin "2") (pinfunction "QC_2") (pintype "tri_state"))
      (node (ref "SR_OUT2") (pin "5") (pinfunction "5_5") (pintype "passive"))
    )
    (net (code "130") (name "Q12") (class "Default")
      (node (ref "IC3") (pin "3") (pinfunction "QD_3") (pintype "tri_state"))
      (node (ref "SR_OUT2") (pin "6") (pinfunction "6_6") (pintype "passive"))
    )
    (net (code "131") (name "Q13") (class "Default")
      (node (ref "IC3") (pin "4") (pinfunction "QE_4") (pintype "tri_state"))
      (node (ref "SR_OUT2") (pin "7") (pinfunction "7_7") (pintype "passive"))
    )
    (net (code "132") (name "Q14") (class "Default")
      (node (ref "IC3") (pin "5") (pinfunction "QF_5") (pintype "tri_state"))
      (node (ref "SR_OUT2") (pin "8") (pinfunction "8_8") (pintype "passive"))
    )
    (net (code "133") (name "Q15") (class "Default")
      (node (ref "IC3") (pin "6") (pinfunction "QG_6") (pintype "tri_state"))
      (node (ref "SR_OUT2") (pin "9") (pinfunction "9_9") (pintype "passive"))
    )
    (net (code "134") (name "Q16") (class "Default")
      (node (ref "IC3") (pin "7") (pinfunction "QH_7") (pintype "tri_state"))
      (node (ref "SR_OUT2") (pin "10") (pinfunction "10_10") (pintype "passive"))
    )
    (net (code "135") (name "QS") (class "Default")
      (node (ref "IC2") (pin "9") (pinfunction "QH*_9") (pintype "tri_state"))
      (node (ref "IC3") (pin "14") (pinfunction "SER_14") (pintype "input"))
    )
    (net (code "136") (name "QS2") (class "Default")
      (node (ref "IC3") (pin "9") (pinfunction "QH*_9") (pintype "tri_state"))
      (node (ref "IC5") (pin "14") (pinfunction "SER_14") (pintype "input"))
    )
    (net (code "137") (name "RXN") (class "Default")
      (node (ref "ETH-C4") (pin "2") (pinfunction "2_2") (pintype "passive"))
      (node (ref "ETH-R7") (pin "1") (pinfunction "1_1") (pintype "passive"))
      (node (ref "U2") (pin "5") (pinfunction "RXN_5") (pintype "passive"))
    )
    (net (code "138") (name "RXP") (class "Default")
      (node (ref "ETH-C2") (pin "2") (pinfunction "2_2") (pintype "passive"))
      (node (ref "ETH-R6") (pin "2") (pinfunction "2_2") (pintype "passive"))
      (node (ref "U2") (pin "6") (pinfunction "RXP_6") (pintype "passive"))
    )
    (net (code "139") (name "SD_CS") (class "Default")
      (node (ref "STM_CHIP") (pin "53") (pinfunction "PC12_53") (pintype "bidirectional"))
      (node (ref "U$4") (pin "SD_CS") (pinfunction "SD_CS_SD_CS") (pintype "passive"))
    )
    (net (code "140") (name "SERIAL_RX") (class "Default")
      (node (ref "STM-USART") (pin "3") (pinfunction "3_3") (pintype "passive"))
      (node (ref "STM_CHIP") (pin "43") (pinfunction "PA10_43") (pintype "bidirectional"))
    )
    (net (code "141") (name "SERIAL_TX") (class "Default")
      (node (ref "STM-USART") (pin "2") (pinfunction "2_2") (pintype "passive"))
      (node (ref "STM_CHIP") (pin "42") (pinfunction "PA9_42") (pintype "bidirectional"))
    )
    (net (code "142") (name "SIM900_PWRKEY") (class "Default")
      (node (ref "IC1") (pin "P$1") (pinfunction "PWRKEY_P$1") (pintype "power_in"))
      (node (ref "SIM900-T3") (pin "C") (pinfunction "C_C") (pintype "passive"))
    )
    (net (code "143") (name "SIM900_RESET") (class "Default")
      (node (ref "IC1") (pin "P$16") (pinfunction "NRESET_P$16") (pintype "bidirectional"))
      (node (ref "SIM900-T4") (pin "C") (pinfunction "C_C") (pintype "passive"))
    )
    (net (code "144") (name "SIM_NETLIGHT") (class "Default")
      (node (ref "IC1") (pin "P$52") (pinfunction "NETLIGHT_P$52") (pintype "bidirectional"))
      (node (ref "SIM900-R8") (pin "2") (pinfunction "2_2") (pintype "passive"))
    )
    (net (code "145") (name "SIM_PWRKEY") (class "Default")
      (node (ref "SIM900-R10") (pin "1") (pinfunction "1_1") (pintype "passive"))
      (node (ref "STM_CHIP") (pin "40") (pinfunction "PC9_40") (pintype "bidirectional"))
    )
    (net (code "146") (name "SIM_RESET") (class "Default")
      (node (ref "SIM900-R11") (pin "1") (pinfunction "1_1") (pintype "passive"))
      (node (ref "STM_CHIP") (pin "50") (pinfunction "PA15_50") (pintype "bidirectional"))
    )
    (net (code "147") (name "SIM_RX") (class "Default")
      (node (ref "IC1") (pin "P$10") (pinfunction "RXD_P$10") (pintype "input"))
      (node (ref "STM_CHIP") (pin "51") (pinfunction "PC10_51") (pintype "bidirectional"))
    )
    (net (code "148") (name "SIM_STATUS") (class "Default")
      (node (ref "IC1") (pin "P$66") (pinfunction "STATUS_P$66") (pintype "bidirectional"))
      (node (ref "SIM900-R5") (pin "2") (pinfunction "2_2") (pintype "passive"))
    )
    (net (code "149") (name "SIM_TX") (class "Default")
      (node (ref "IC1") (pin "P$9") (pinfunction "TXD_P$9") (pintype "output"))
      (node (ref "STM_CHIP") (pin "52") (pinfunction "PC11_52") (pintype "bidirectional"))
    )
    (net (code "150") (name "SR_DS") (class "Default")
      (node (ref "IC2") (pin "14") (pinfunction "SER_14") (pintype "input"))
      (node (ref "STM_CHIP") (pin "8") (pinfunction "PC0_8") (pintype "bidirectional"))
    )
    (net (code "151") (name "SR_RST") (class "Default")
      (node (ref "IC2") (pin "10") (pinfunction "SCL_10") (pintype "input"))
      (node (ref "IC3") (pin "10") (pinfunction "SCL_10") (pintype "input"))
      (node (ref "IC5") (pin "10") (pinfunction "SCL_10") (pintype "input"))
      (node (ref "STM_CHIP") (pin "11") (pinfunction "PC3_11") (pintype "bidirectional"))
    )
    (net (code "152") (name "SR_SHCP") (class "Default")
      (node (ref "IC2") (pin "11") (pinfunction "SCK_11") (pintype "input"))
      (node (ref "IC3") (pin "11") (pinfunction "SCK_11") (pintype "input"))
      (node (ref "IC5") (pin "11") (pinfunction "SCK_11") (pintype "input"))
      (node (ref "STM_CHIP") (pin "10") (pinfunction "PC2_10") (pintype "bidirectional"))
    )
    (net (code "153") (name "SR_STCP") (class "Default")
      (node (ref "IC2") (pin "12") (pinfunction "RCK_12") (pintype "input"))
      (node (ref "IC3") (pin "12") (pinfunction "RCK_12") (pintype "input"))
      (node (ref "IC5") (pin "12") (pinfunction "RCK_12") (pintype "input"))
      (node (ref "STM_CHIP") (pin "9") (pinfunction "PC1_9") (pintype "bidirectional"))
    )
    (net (code "154") (name "SWD_NRST") (class "Default")
      (node (ref "S1") (pin "1") (pinfunction "1_1") (pintype "passive"))
      (node (ref "S1") (pin "2") (pinfunction "2_2") (pintype "passive"))
      (node (ref "STM-C8") (pin "1") (pinfunction "1_1") (pintype "passive"))
      (node (ref "STM_CHIP") (pin "7") (pinfunction "NRST_7") (pintype "bidirectional"))
    )
    (net (code "155") (name "SWD_TCK") (class "Default")
      (node (ref "STM-SWD") (pin "2") (pinfunction "2_2") (pintype "passive"))
      (node (ref "STM_CHIP") (pin "49") (pinfunction "PA14_49") (pintype "bidirectional"))
    )
    (net (code "156") (name "SWD_TMS") (class "Default")
      (node (ref "STM-SWD") (pin "4") (pinfunction "4_4") (pintype "passive"))
      (node (ref "STM_CHIP") (pin "46") (pinfunction "PA13_46") (pintype "bidirectional"))
    )
    (net (code "157") (name "SW_PIN") (class "Default")
      (node (ref "STM_CHIP") (pin "30") (pinfunction "PB11_30") (pintype "bidirectional"))
      (node (ref "U$6") (pin "3") (pinfunction "4_3") (pintype "passive"))
    )
    (net (code "158") (name "TXN") (class "Default")
      (node (ref "ETH-R2") (pin "1") (pinfunction "1_1") (pintype "passive"))
      (node (ref "ETHERNET") (pin "2") (pinfunction "TX-_2") (pintype "bidirectional"))
      (node (ref "U2") (pin "1") (pinfunction "TXN_1") (pintype "passive"))
    )
    (net (code "159") (name "TXP") (class "Default")
      (node (ref "ETH-R1") (pin "1") (pinfunction "1_1") (pintype "passive"))
      (node (ref "ETHERNET") (pin "1") (pinfunction "TX+_1") (pintype "bidirectional"))
      (node (ref "U2") (pin "2") (pinfunction "TXP_2") (pintype "passive"))
    )
    (net (code "160") (name "USIM_CLK") (class "Default")
      (node (ref "SIM900-R2") (pin "2") (pinfunction "2_2") (pintype "passive"))
      (node (ref "SIM_HOLDER") (pin "3") (pinfunction "CLK_3") (pintype "bidirectional"))
    )
    (net (code "161") (name "USIM_DATA") (class "Default")
      (node (ref "SIM900-R3") (pin "2") (pinfunction "2_2") (pintype "passive"))
      (node (ref "SIM_HOLDER") (pin "4") (pinfunction "I/O_4") (pintype "bidirectional"))
    )
    (net (code "162") (name "USIM_RESET") (class "Default")
      (node (ref "SIM900-R1") (pin "2") (pinfunction "2_2") (pintype "passive"))
      (node (ref "SIM_HOLDER") (pin "2") (pinfunction "RST_2") (pintype "bidirectional"))
    )
    (net (code "163") (name "USIM_VCC") (class "Default")
      (node (ref "IC1") (pin "P$30") (pinfunction "SIM_VDD_P$30") (pintype "power_in"))
      (node (ref "SIM900-C4") (pin "1") (pinfunction "1_1") (pintype "passive"))
      (node (ref "SIM900-C5") (pin "1") (pinfunction "1_1") (pintype "passive"))
      (node (ref "SIM_C1") (pin "2") (pinfunction "2_2") (pintype "passive"))
      (node (ref "SIM_C2") (pin "2") (pinfunction "2_2") (pintype "passive"))
      (node (ref "SIM_HOLDER") (pin "1") (pinfunction "VCC_1") (pintype "bidirectional"))
    )
    (net (code "164") (name "VBAT") (class "Default")
      (node (ref "BAT1") (pin "1") (pinfunction "+_1") (pintype "power_in"))
      (node (ref "STM_CHIP") (pin "1") (pinfunction "VLCD_1") (pintype "power_in"))
    )
    (net (code "165") (name "VCC") (class "Default")
      (node (ref "ETH-R1") (pin "2") (pinfunction "2_2") (pintype "passive"))
      (node (ref "ETH-R2") (pin "2") (pinfunction "2_2") (pintype "passive"))
      (node (ref "ETH-R3") (pin "2") (pinfunction "2_2") (pintype "passive"))
      (node (ref "STM-C9") (pin "1") (pinfunction "1_1") (pintype "passive"))
      (node (ref "STM-L1") (pin "2") (pinfunction "2_2") (pintype "passive"))
      (node (ref "STM_CHIP") (pin "13") (pinfunction "VDDA_13") (pintype "power_in"))
      (node (ref "SYS-C4") (pin "1") (pinfunction "1_1") (pintype "passive"))
      (node (ref "SYS-R2") (pin "2") (pinfunction "2_2") (pintype "passive"))
      (node (ref "U2") (pin "11") (pinfunction "AVDD_11") (pintype "passive"))
      (node (ref "U2") (pin "15") (pinfunction "AVDD_15") (pintype "passive"))
      (node (ref "U2") (pin "17") (pinfunction "AVDD_17") (pintype "passive"))
      (node (ref "U2") (pin "21") (pinfunction "AVDD_21") (pintype "passive"))
      (node (ref "U2") (pin "4") (pinfunction "AVDD_4") (pintype "passive"))
      (node (ref "U2") (pin "8") (pinfunction "AVDD_8") (pintype "passive"))
      (node (ref "W5500-C10") (pin "1") (pinfunction "1_1") (pintype "passive"))
      (node (ref "W5500-C11") (pin "1") (pinfunction "1_1") (pintype "passive"))
      (node (ref "W5500-C12") (pin "+") (pinfunction "+_+") (pintype "passive"))
      (node (ref "W5500-C6") (pin "1") (pinfunction "1_1") (pintype "passive"))
      (node (ref "W5500-C7") (pin "1") (pinfunction "1_1") (pintype "passive"))
      (node (ref "W5500-C8") (pin "1") (pinfunction "1_1") (pintype "passive"))
      (node (ref "W5500-C9") (pin "1") (pinfunction "1_1") (pintype "passive"))
    )
    (net (code "166") (name "VDD") (class "Default")
      (node (ref "DHT-R1") (pin "1") (pinfunction "1_1") (pintype "passive"))
      (node (ref "ESP-VDD") (pin "1") (pinfunction "1_1") (pintype "passive"))
      (node (ref "ETHERNET") (pin "12") (pinfunction "LED2_A_12") (pintype "bidirectional"))
      (node (ref "ETHERNET") (pin "9") (pinfunction "LED1_A_9") (pintype "bidirectional"))
      (node (ref "IC2") (pin "16") (pinfunction "VCC_16") (pintype "power_in"))
      (node (ref "IC3") (pin "16") (pinfunction "VCC_16") (pintype "power_in"))
      (node (ref "IC5") (pin "16") (pinfunction "VCC_16") (pintype "power_in"))
      (node (ref "LCD-R1") (pin "2") (pinfunction "2_2") (pintype "passive"))
      (node (ref "PWR-SWT") (pin "1") (pinfunction "1_1") (pintype "passive"))
      (node (ref "R1") (pin "1") (pinfunction "1_1") (pintype "passive"))
      (node (ref "SENSOR-DHT") (pin "1") (pinfunction "1_1") (pintype "passive"))
      (node (ref "SIM900-R4") (pin "2") (pinfunction "2_2") (pintype "passive"))
      (node (ref "SIM900-R7") (pin "2") (pinfunction "2_2") (pintype "passive"))
      (node (ref "STM-C1") (pin "2") (pinfunction "2_2") (pintype "passive"))
      (node (ref "STM-C10") (pin "1") (pinfunction "1_1") (pintype "passive"))
      (node (ref "STM-C11") (pin "1") (pinfunction "1_1") (pintype "passive"))
      (node (ref "STM-C12") (pin "1") (pinfunction "1_1") (pintype "passive"))
      (node (ref "STM-C13") (pin "1") (pinfunction "1_1") (pintype "passive"))
      (node (ref "STM-L1") (pin "1") (pinfunction "1_1") (pintype "passive"))
      (node (ref "STM-SWD") (pin "1") (pinfunction "1_1") (pintype "passive"))
      (node (ref "STM-USART") (pin "1") (pinfunction "1_1") (pintype "passive"))
      (node (ref "STM_CHIP") (pin "19") (pinfunction "VDD_4_19") (pintype "power_in"))
      (node (ref "STM_CHIP") (pin "32") (pinfunction "VDD_1_32") (pintype "power_in"))
      (node (ref "STM_CHIP") (pin "48") (pinfunction "VDD_2_48") (pintype "power_in"))
      (node (ref "STM_CHIP") (pin "64") (pinfunction "VDD_3_64") (pintype "power_in"))
      (node (ref "SYS-C3") (pin "1") (pinfunction "1_1") (pintype "passive"))
      (node (ref "SYS-L2") (pin "2") (pinfunction "2_2") (pintype "passive"))
      (node (ref "SYS-R2") (pin "1") (pinfunction "1_1") (pintype "passive"))
      (node (ref "U$4") (pin "LCD_VCC") (pinfunction "LCD_VCC_LCD_VCC") (pintype "passive"))
      (node (ref "U2") (pin "28") (pinfunction "VDD_28") (pintype "passive"))
      (node (ref "W5500-C13") (pin "+") (pinfunction "+_+") (pintype "passive"))
      (node (ref "W5500-C5") (pin "1") (pinfunction "1_1") (pintype "passive"))
      (node (ref "W5500-R1") (pin "1") (pinfunction "1_1") (pintype "passive"))
      (node (ref "W5500-R13") (pin "2") (pinfunction "2_2") (pintype "passive"))
      (node (ref "W5500-R2") (pin "1") (pinfunction "1_1") (pintype "passive"))
      (node (ref "W5500-R3") (pin "1") (pinfunction "1_1") (pintype "passive"))
      (node (ref "W5500-R9") (pin "2") (pinfunction "2_2") (pintype "passive"))
    )
    (net (code "167") (name "VESP") (class "Default")
      (node (ref "ESP-C1") (pin "1") (pinfunction "1_1") (pintype "passive"))
      (node (ref "ESP-GPIO0") (pin "1") (pinfunction "1_1") (pintype "passive"))
      (node (ref "ESP-VDD") (pin "2") (pinfunction "2_2") (pintype "passive"))
      (node (ref "U$5") (pin "CH_PD") (pinfunction "CH_PD_CH_PD") (pintype "bidirectional"))
      (node (ref "U$5") (pin "VCC") (pinfunction "VCC_VCC") (pintype "power_in"))
    )
    (net (code "168") (name "VEXT") (class "Default")
      (node (ref "ESP-UART-A") (pin "1") (pinfunction "1_1") (pintype "passive"))
      (node (ref "ESP-VDD") (pin "3") (pinfunction "3_3") (pintype "passive"))
    )
    (net (code "169") (name "unconnected-(CT1-Pad3)") (class "Default")
      (node (ref "CT1") (pin "3") (pinfunction "3_3") (pintype "passive"))
    )
    (net (code "170") (name "unconnected-(CT1-Pad4)") (class "Default")
      (node (ref "CT1") (pin "4") (pinfunction "4_4") (pintype "passive"))
    )
    (net (code "171") (name "unconnected-(CT2-Pad3)") (class "Default")
      (node (ref "CT2") (pin "3") (pinfunction "3_3") (pintype "passive"))
    )
    (net (code "172") (name "unconnected-(CT2-Pad4)") (class "Default")
      (node (ref "CT2") (pin "4") (pinfunction "4_4") (pintype "passive"))
    )
    (net (code "173") (name "unconnected-(CT3-Pad3)") (class "Default")
      (node (ref "CT3") (pin "3") (pinfunction "3_3") (pintype "passive"))
    )
    (net (code "174") (name "unconnected-(CT3-Pad4)") (class "Default")
      (node (ref "CT3") (pin "4") (pinfunction "4_4") (pintype "passive"))
    )
    (net (code "175") (name "unconnected-(IC1-ADC-PadP$25)") (class "Default")
      (node (ref "IC1") (pin "P$25") (pinfunction "ADC_P$25") (pintype "bidirectional"))
    )
    (net (code "176") (name "unconnected-(IC1-CTS-PadP$7)") (class "Default")
      (node (ref "IC1") (pin "P$7") (pinfunction "CTS_P$7") (pintype "output"))
    )
    (net (code "177") (name "unconnected-(IC1-DBG_RXD-PadP$28)") (class "Default")
      (node (ref "IC1") (pin "P$28") (pinfunction "DBG_RXD_P$28") (pintype "input"))
    )
    (net (code "178") (name "unconnected-(IC1-DBG_TXD-PadP$27)") (class "Default")
      (node (ref "IC1") (pin "P$27") (pinfunction "DBG_TXD_P$27") (pintype "output"))
    )
    (net (code "179") (name "unconnected-(IC1-DCD-PadP$5)") (class "Default")
      (node (ref "IC1") (pin "P$5") (pinfunction "DCD_P$5") (pintype "output"))
    )
    (net (code "180") (name "unconnected-(IC1-DISP_CLK-PadP$11)") (class "Default")
      (node (ref "IC1") (pin "P$11") (pinfunction "DISP_CLK_P$11") (pintype "bidirectional"))
    )
    (net (code "181") (name "unconnected-(IC1-DISP_CS-PadP$14)") (class "Default")
      (node (ref "IC1") (pin "P$14") (pinfunction "DISP_CS_P$14") (pintype "bidirectional"))
    )
    (net (code "182") (name "unconnected-(IC1-DISP_DATA-PadP$12)") (class "Default")
      (node (ref "IC1") (pin "P$12") (pinfunction "DISP_DATA_P$12") (pintype "bidirectional"))
    )
    (net (code "183") (name "unconnected-(IC1-DISP_DC-PadP$13)") (class "Default")
      (node (ref "IC1") (pin "P$13") (pinfunction "DISP_DC_P$13") (pintype "bidirectional"))
    )
    (net (code "184") (name "unconnected-(IC1-DTR-PadP$3)") (class "Default")
      (node (ref "IC1") (pin "P$3") (pinfunction "DTR_P$3") (pintype "input"))
    )
    (net (code "185") (name "unconnected-(IC1-GPIO1{slash}KBR4-PadP$40)") (class "Default")
      (node (ref "IC1") (pin "P$40") (pinfunction "GPIO1/KBR4_P$40") (pintype "bidirectional"))
    )
    (net (code "186") (name "unconnected-(IC1-GPIO2{slash}KBR3-PadP$41)") (class "Default")
      (node (ref "IC1") (pin "P$41") (pinfunction "GPIO2/KBR3_P$41") (pintype "bidirectional"))
    )
    (net (code "187") (name "unconnected-(IC1-GPIO3{slash}KBR2-PadP$42)") (class "Default")
      (node (ref "IC1") (pin "P$42") (pinfunction "GPIO3/KBR2_P$42") (pintype "bidirectional"))
    )
    (net (code "188") (name "unconnected-(IC1-GPIO4{slash}KBR1-PadP$43)") (class "Default")
      (node (ref "IC1") (pin "P$43") (pinfunction "GPIO4/KBR1_P$43") (pintype "bidirectional"))
    )
    (net (code "189") (name "unconnected-(IC1-GPIO5{slash}KBR0-PadP$44)") (class "Default")
      (node (ref "IC1") (pin "P$44") (pinfunction "GPIO5/KBR0_P$44") (pintype "bidirectional"))
    )
    (net (code "190") (name "unconnected-(IC1-GPIO6{slash}KBC4-PadP$47)") (class "Default")
      (node (ref "IC1") (pin "P$47") (pinfunction "GPIO6/KBC4_P$47") (pintype "bidirectional"))
    )
    (net (code "191") (name "unconnected-(IC1-GPIO7{slash}KBC3-PadP$48)") (class "Default")
      (node (ref "IC1") (pin "P$48") (pinfunction "GPIO7/KBC3_P$48") (pintype "bidirectional"))
    )
    (net (code "192") (name "unconnected-(IC1-GPIO8{slash}KBC2-PadP$49)") (class "Default")
      (node (ref "IC1") (pin "P$49") (pinfunction "GPIO8/KBC2_P$49") (pintype "bidirectional"))
    )
    (net (code "193") (name "unconnected-(IC1-GPIO9{slash}KBC1-PadP$50)") (class "Default")
      (node (ref "IC1") (pin "P$50") (pinfunction "GPIO9/KBC1_P$50") (pintype "bidirectional"))
    )
    (net (code "194") (name "unconnected-(IC1-GPIO10-PadP$51)") (class "Default")
      (node (ref "IC1") (pin "P$51") (pinfunction "GPIO10_P$51") (pintype "bidirectional"))
    )
    (net (code "195") (name "unconnected-(IC1-LINEIN_L-PadP$24)") (class "Default")
      (node (ref "IC1") (pin "P$24") (pinfunction "LINEIN_L_P$24") (pintype "bidirectional"))
    )
    (net (code "196") (name "unconnected-(IC1-LINEIN_R-PadP$23)") (class "Default")
      (node (ref "IC1") (pin "P$23") (pinfunction "LINEIN_R_P$23") (pintype "bidirectional"))
    )
    (net (code "197") (name "unconnected-(IC1-MIC_N-PadP$20)") (class "Default")
      (node (ref "IC1") (pin "P$20") (pinfunction "MIC_N_P$20") (pintype "bidirectional"))
    )
    (net (code "198") (name "unconnected-(IC1-MIC_P-PadP$19)") (class "Default")
      (node (ref "IC1") (pin "P$19") (pinfunction "MIC_P_P$19") (pintype "bidirectional"))
    )
    (net (code "199") (name "unconnected-(IC1-NC-PadP$2)") (class "Default")
      (node (ref "IC1") (pin "P$2") (pinfunction "NC_P$2") (pintype "no_connect"))
    )
    (net (code "200") (name "unconnected-(IC1-NC-PadP$6)") (class "Default")
      (node (ref "IC1") (pin "P$6") (pinfunction "NC_P$6") (pintype "no_connect"))
    )
    (net (code "201") (name "unconnected-(IC1-PWM1-PadP$35)") (class "Default")
      (node (ref "IC1") (pin "P$35") (pinfunction "PWM1_P$35") (pintype "bidirectional"))
    )
    (net (code "202") (name "unconnected-(IC1-PWM2-PadP$36)") (class "Default")
      (node (ref "IC1") (pin "P$36") (pinfunction "PWM2_P$36") (pintype "bidirectional"))
    )
    (net (code "203") (name "unconnected-(IC1-RI-PadP$4)") (class "Default")
      (node (ref "IC1") (pin "P$4") (pinfunction "RI_P$4") (pintype "output"))
    )
    (net (code "204") (name "unconnected-(IC1-RTS-PadP$8)") (class "Default")
      (node (ref "IC1") (pin "P$8") (pinfunction "RTS_P$8") (pintype "input"))
    )
    (net (code "205") (name "unconnected-(IC1-SCL-PadP$38)") (class "Default")
      (node (ref "IC1") (pin "P$38") (pinfunction "SCL_P$38") (pintype "bidirectional"))
    )
    (net (code "206") (name "unconnected-(IC1-SDA-PadP$37)") (class "Default")
      (node (ref "IC1") (pin "P$37") (pinfunction "SDA_P$37") (pintype "bidirectional"))
    )
    (net (code "207") (name "unconnected-(IC1-SIM_PRESENCE-PadP$34)") (class "Default")
      (node (ref "IC1") (pin "P$34") (pinfunction "SIM_PRESENCE_P$34") (pintype "bidirectional"))
    )
    (net (code "208") (name "unconnected-(IC1-SPK_N-PadP$22)") (class "Default")
      (node (ref "IC1") (pin "P$22") (pinfunction "SPK_N_P$22") (pintype "bidirectional"))
    )
    (net (code "209") (name "unconnected-(IC1-SPK_P-PadP$21)") (class "Default")
      (node (ref "IC1") (pin "P$21") (pinfunction "SPK_P_P$21") (pintype "bidirectional"))
    )
    (net (code "210") (name "unconnected-(IC1-VDD_EXT-PadP$15)") (class "Default")
      (node (ref "IC1") (pin "P$15") (pinfunction "VDD_EXT_P$15") (pintype "bidirectional"))
    )
    (net (code "211") (name "unconnected-(IC5A-QE-Pad4)") (class "Default")
      (node (ref "IC5") (pin "4") (pinfunction "QE_4") (pintype "tri_state"))
    )
    (net (code "212") (name "unconnected-(IC5A-QF-Pad5)") (class "Default")
      (node (ref "IC5") (pin "5") (pinfunction "QF_5") (pintype "tri_state"))
    )
    (net (code "213") (name "unconnected-(IC5A-QG-Pad6)") (class "Default")
      (node (ref "IC5") (pin "6") (pinfunction "QG_6") (pintype "tri_state"))
    )
    (net (code "214") (name "unconnected-(IC5A-QH*-Pad9)") (class "Default")
      (node (ref "IC5") (pin "9") (pinfunction "QH*_9") (pintype "tri_state"))
    )
    (net (code "215") (name "unconnected-(IC5A-QH-Pad7)") (class "Default")
      (node (ref "IC5") (pin "7") (pinfunction "QH_7") (pintype "tri_state"))
    )
    (net (code "216") (name "unconnected-(SENSOR-DHT-Pad3)") (class "Default")
      (node (ref "SENSOR-DHT") (pin "3") (pinfunction "3_3") (pintype "passive"))
    )
    (net (code "217") (name "unconnected-(SIM_HOLDER-VPP-Pad5)") (class "Default")
      (node (ref "SIM_HOLDER") (pin "5") (pinfunction "VPP_5") (pintype "bidirectional"))
    )
    (net (code "218") (name "unconnected-(STM_CHIP-BOOT0-Pad60)") (class "Default")
      (node (ref "STM_CHIP") (pin "60") (pinfunction "BOOT0_60") (pintype "input"))
    )
    (net (code "219") (name "unconnected-(STM_CHIP-PA0-WKUP1-Pad14)") (class "Default")
      (node (ref "STM_CHIP") (pin "14") (pinfunction "PA0-WKUP1_14") (pintype "bidirectional"))
    )
    (net (code "220") (name "unconnected-(STM_CHIP-PA8-Pad41)") (class "Default")
      (node (ref "STM_CHIP") (pin "41") (pinfunction "PA8_41") (pintype "bidirectional"))
    )
    (net (code "221") (name "unconnected-(STM_CHIP-PA11-Pad44)") (class "Default")
      (node (ref "STM_CHIP") (pin "44") (pinfunction "PA11_44") (pintype "bidirectional"))
    )
    (net (code "222") (name "unconnected-(STM_CHIP-PA12-Pad45)") (class "Default")
      (node (ref "STM_CHIP") (pin "45") (pinfunction "PA12_45") (pintype "bidirectional"))
    )
    (net (code "223") (name "unconnected-(STM_CHIP-PB2-Pad28)") (class "Default")
      (node (ref "STM_CHIP") (pin "28") (pinfunction "PB2_28") (pintype "bidirectional"))
    )
    (net (code "224") (name "unconnected-(STM_CHIP-PB3-Pad55)") (class "Default")
      (node (ref "STM_CHIP") (pin "55") (pinfunction "PB3_55") (pintype "bidirectional"))
    )
    (net (code "225") (name "unconnected-(STM_CHIP-PC7-Pad38)") (class "Default")
      (node (ref "STM_CHIP") (pin "38") (pinfunction "PC7_38") (pintype "bidirectional"))
    )
    (net (code "226") (name "unconnected-(STM_CHIP-PC13-RTC_AF1-WKUP2-Pad2)") (class "Default")
      (node (ref "STM_CHIP") (pin "2") (pinfunction "PC13-RTC_AF1-WKUP2_2") (pintype "bidirectional"))
    )
    (net (code "227") (name "unconnected-(STM_CHIP-PH0_-OSC_IN-Pad5)") (class "Default")
      (node (ref "STM_CHIP") (pin "5") (pinfunction "PH0_-OSC_IN_5") (pintype "bidirectional"))
    )
    (net (code "228") (name "unconnected-(STM_CHIP-PH1-_OSC_OUT-Pad6)") (class "Default")
      (node (ref "STM_CHIP") (pin "6") (pinfunction "PH1-_OSC_OUT_6") (pintype "bidirectional"))
    )
    (net (code "229") (name "unconnected-(U$5-GPIO2-PadGPIO02)") (class "Default")
      (node (ref "U$5") (pin "GPIO02") (pinfunction "GPIO2_GPIO02") (pintype "bidirectional"))
    )
    (net (code "230") (name "unconnected-(U$5-GPIO4-PadGPIO04)") (class "Default")
      (node (ref "U$5") (pin "GPIO04") (pinfunction "GPIO4_GPIO04") (pintype "bidirectional"))
    )
    (net (code "231") (name "unconnected-(U$5-GPIO5-PadGPIO05)") (class "Default")
      (node (ref "U$5") (pin "GPIO05") (pinfunction "GPIO5_GPIO05") (pintype "bidirectional"))
    )
    (net (code "232") (name "unconnected-(U$5-PadADC)") (class "Default")
      (node (ref "U$5") (pin "ADC") (pinfunction "ADC_ADC") (pintype "bidirectional"))
    )
    (net (code "233") (name "unconnected-(U$5-PadGPIO12)") (class "Default")
      (node (ref "U$5") (pin "GPIO12") (pinfunction "GPIO12_GPIO12") (pintype "bidirectional"))
    )
    (net (code "234") (name "unconnected-(U$5-PadGPIO13)") (class "Default")
      (node (ref "U$5") (pin "GPIO13") (pinfunction "GPIO13_GPIO13") (pintype "bidirectional"))
    )
    (net (code "235") (name "unconnected-(U$5-PadGPIO14)") (class "Default")
      (node (ref "U$5") (pin "GPIO14") (pinfunction "GPIO14_GPIO14") (pintype "bidirectional"))
    )
    (net (code "236") (name "unconnected-(U$5-PadGPIO16)") (class "Default")
      (node (ref "U$5") (pin "GPIO16") (pinfunction "GPIO16_GPIO16") (pintype "bidirectional"))
    )
    (net (code "237") (name "unconnected-(U$5-PadREST)") (class "Default")
      (node (ref "U$5") (pin "REST") (pinfunction "REST_REST") (pintype "bidirectional"))
    )
    (net (code "238") (name "unconnected-(U2-DNC-Pad7)") (class "Default")
      (node (ref "U2") (pin "7") (pinfunction "DNC_7") (pintype "passive"))
    )
    (net (code "239") (name "unconnected-(U2-DUPLED-Pad26)") (class "Default")
      (node (ref "U2") (pin "26") (pinfunction "DUPLED_26") (pintype "passive"))
    )
    (net (code "240") (name "unconnected-(U2-INT_N-Pad36)") (class "Default")
      (node (ref "U2") (pin "36") (pinfunction "INT_N_36") (pintype "passive"))
    )
    (net (code "241") (name "unconnected-(U2-NC-Pad12)") (class "Default")
      (node (ref "U2") (pin "12") (pinfunction "NC_12") (pintype "passive"))
    )
    (net (code "242") (name "unconnected-(U2-NC-Pad13)") (class "Default")
      (node (ref "U2") (pin "13") (pinfunction "NC_13") (pintype "passive"))
    )
    (net (code "243") (name "unconnected-(U2-NC-Pad46)") (class "Default")
      (node (ref "U2") (pin "46") (pinfunction "NC_46") (pintype "passive"))
    )
    (net (code "244") (name "unconnected-(U2-NC-Pad47)") (class "Default")
      (node (ref "U2") (pin "47") (pinfunction "NC_47") (pintype "passive"))
    )
    (net (code "245") (name "unconnected-(U2-SPDLED-Pad24)") (class "Default")
      (node (ref "U2") (pin "24") (pinfunction "SPDLED_24") (pintype "passive"))
    )
    (net (code "246") (name "unconnected-(U2-VBG-Pad18)") (class "Default")
      (node (ref "U2") (pin "18") (pinfunction "VBG_18") (pintype "passive"))
    )
  )
)
